# plugwatch.net
KiCad netlist of a schematic drawn in EAGLE
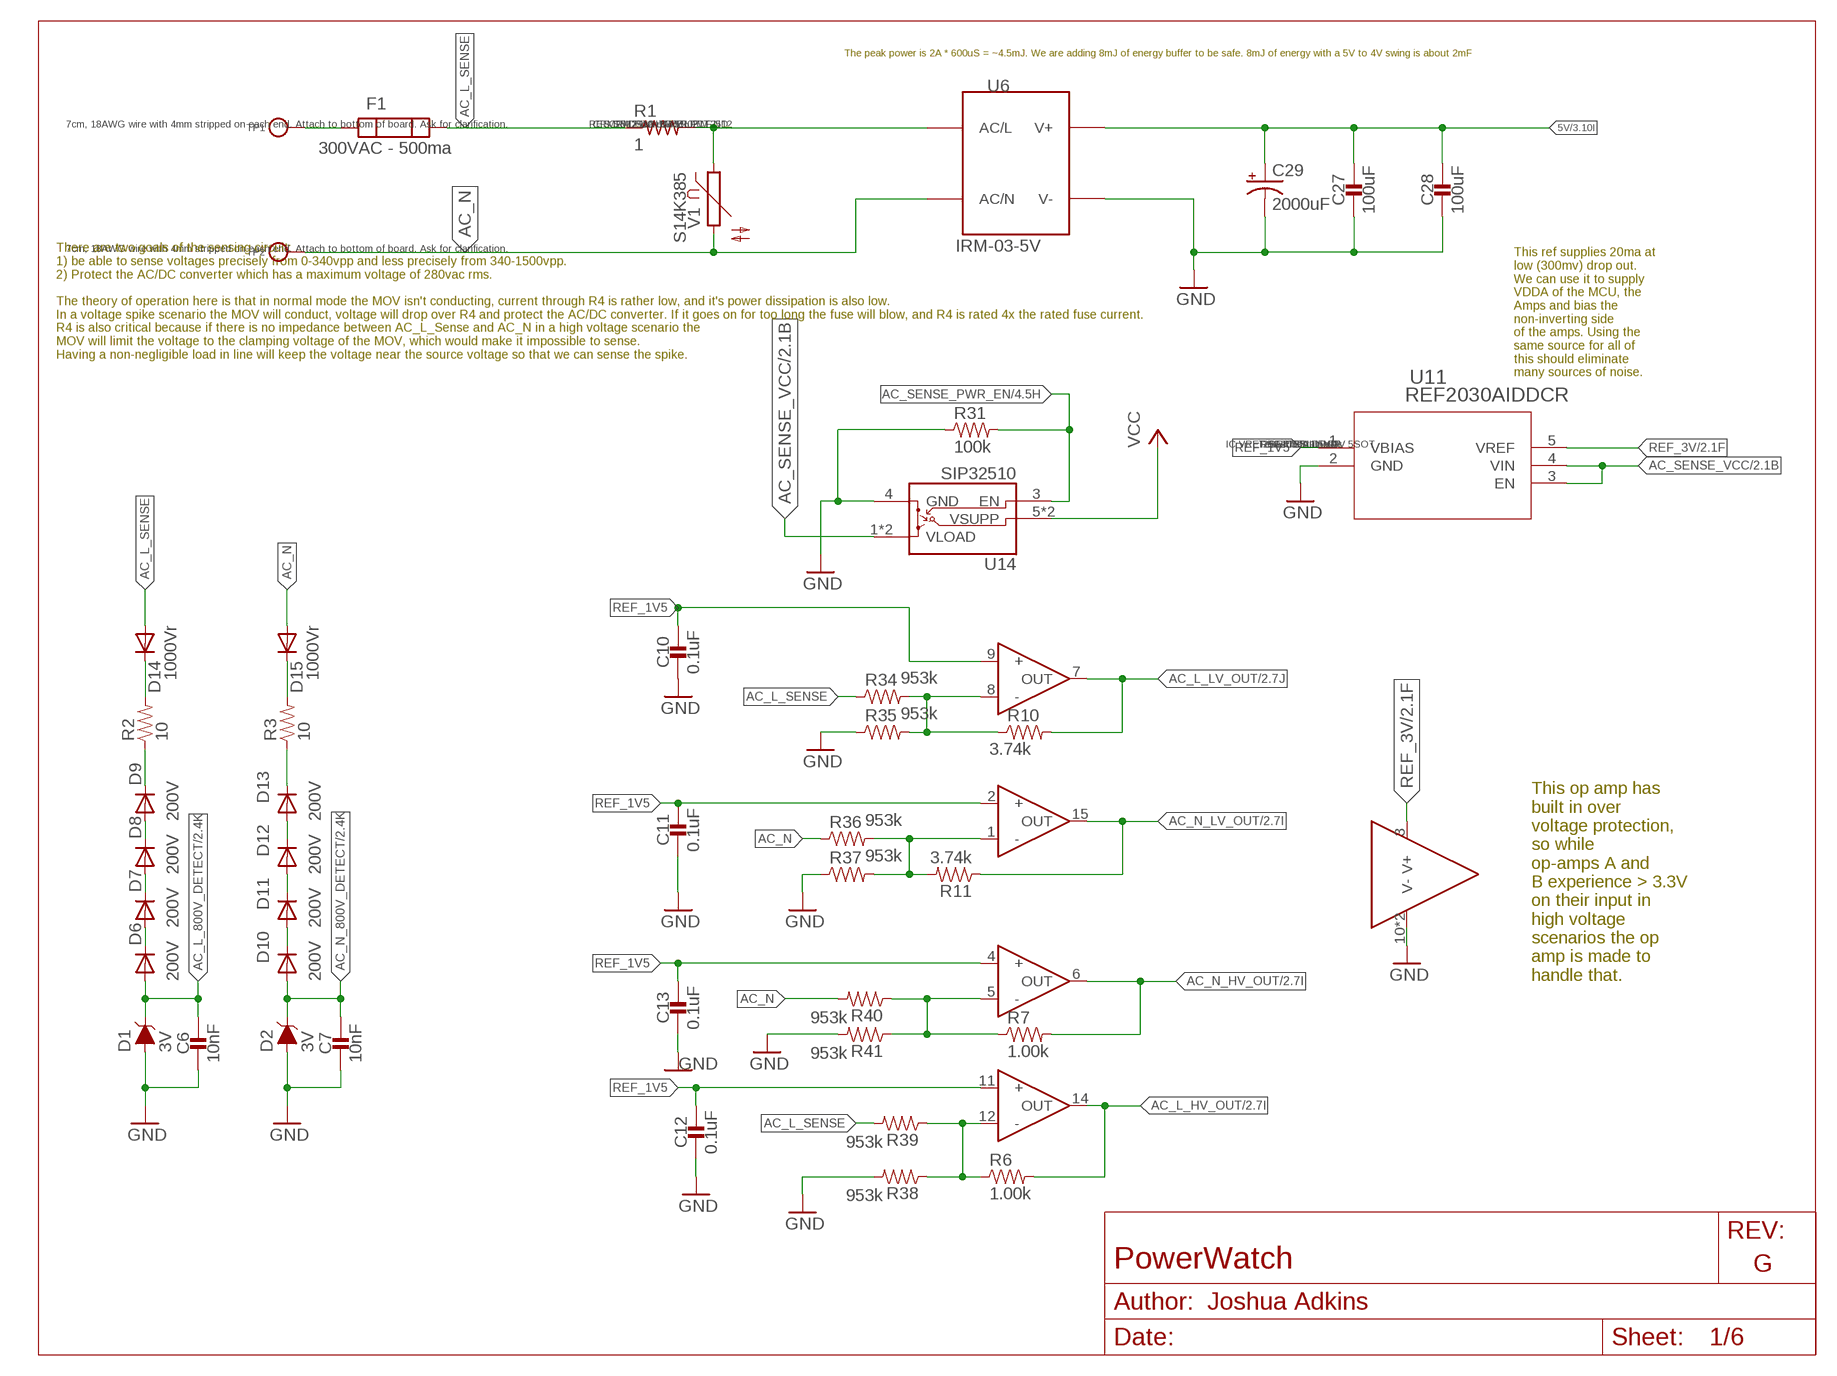
[diagram p0: schematic, sheet 1]
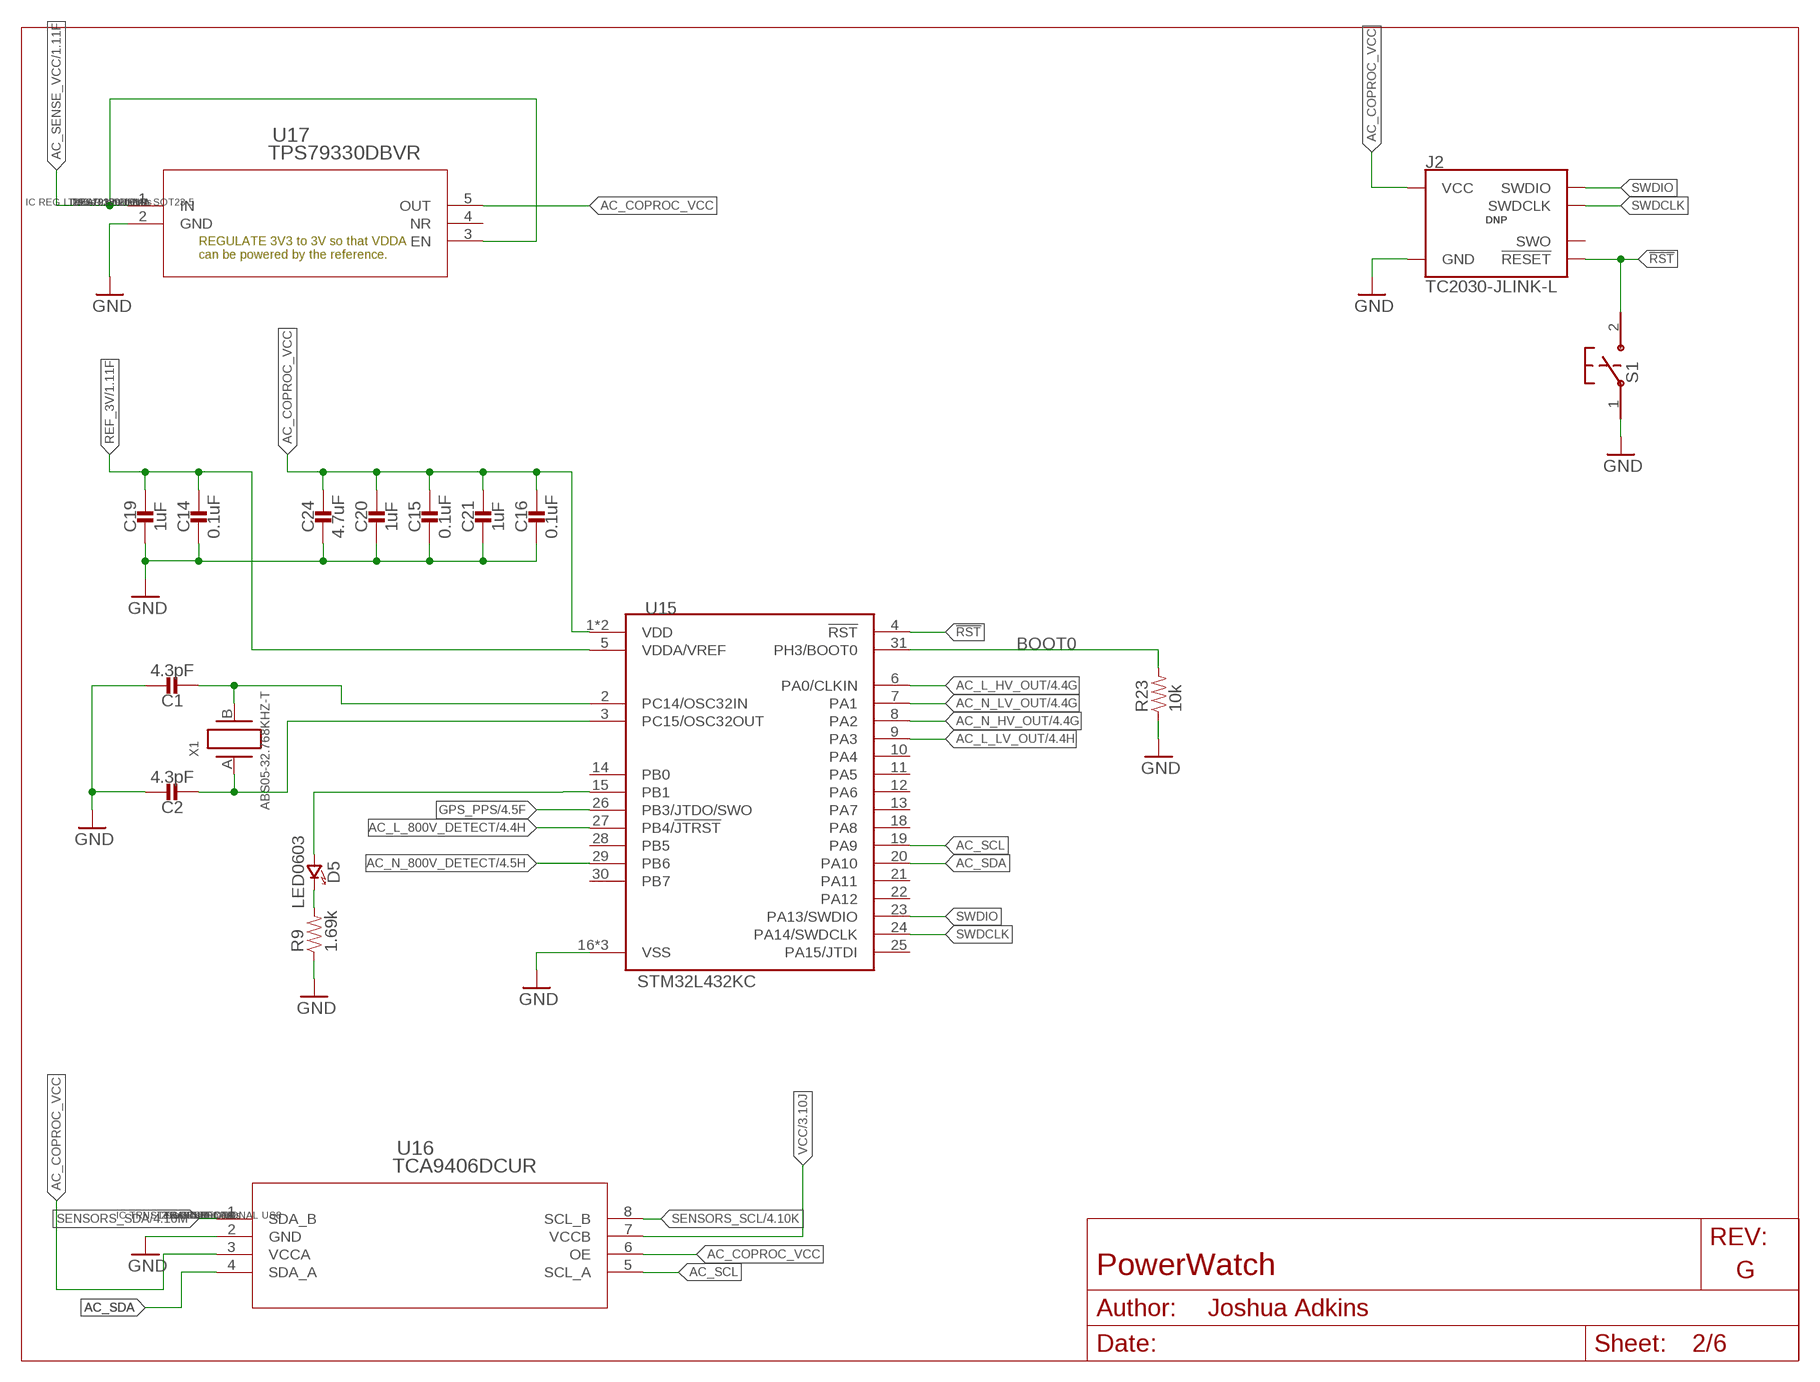
[diagram p1: schematic, sheet 2]
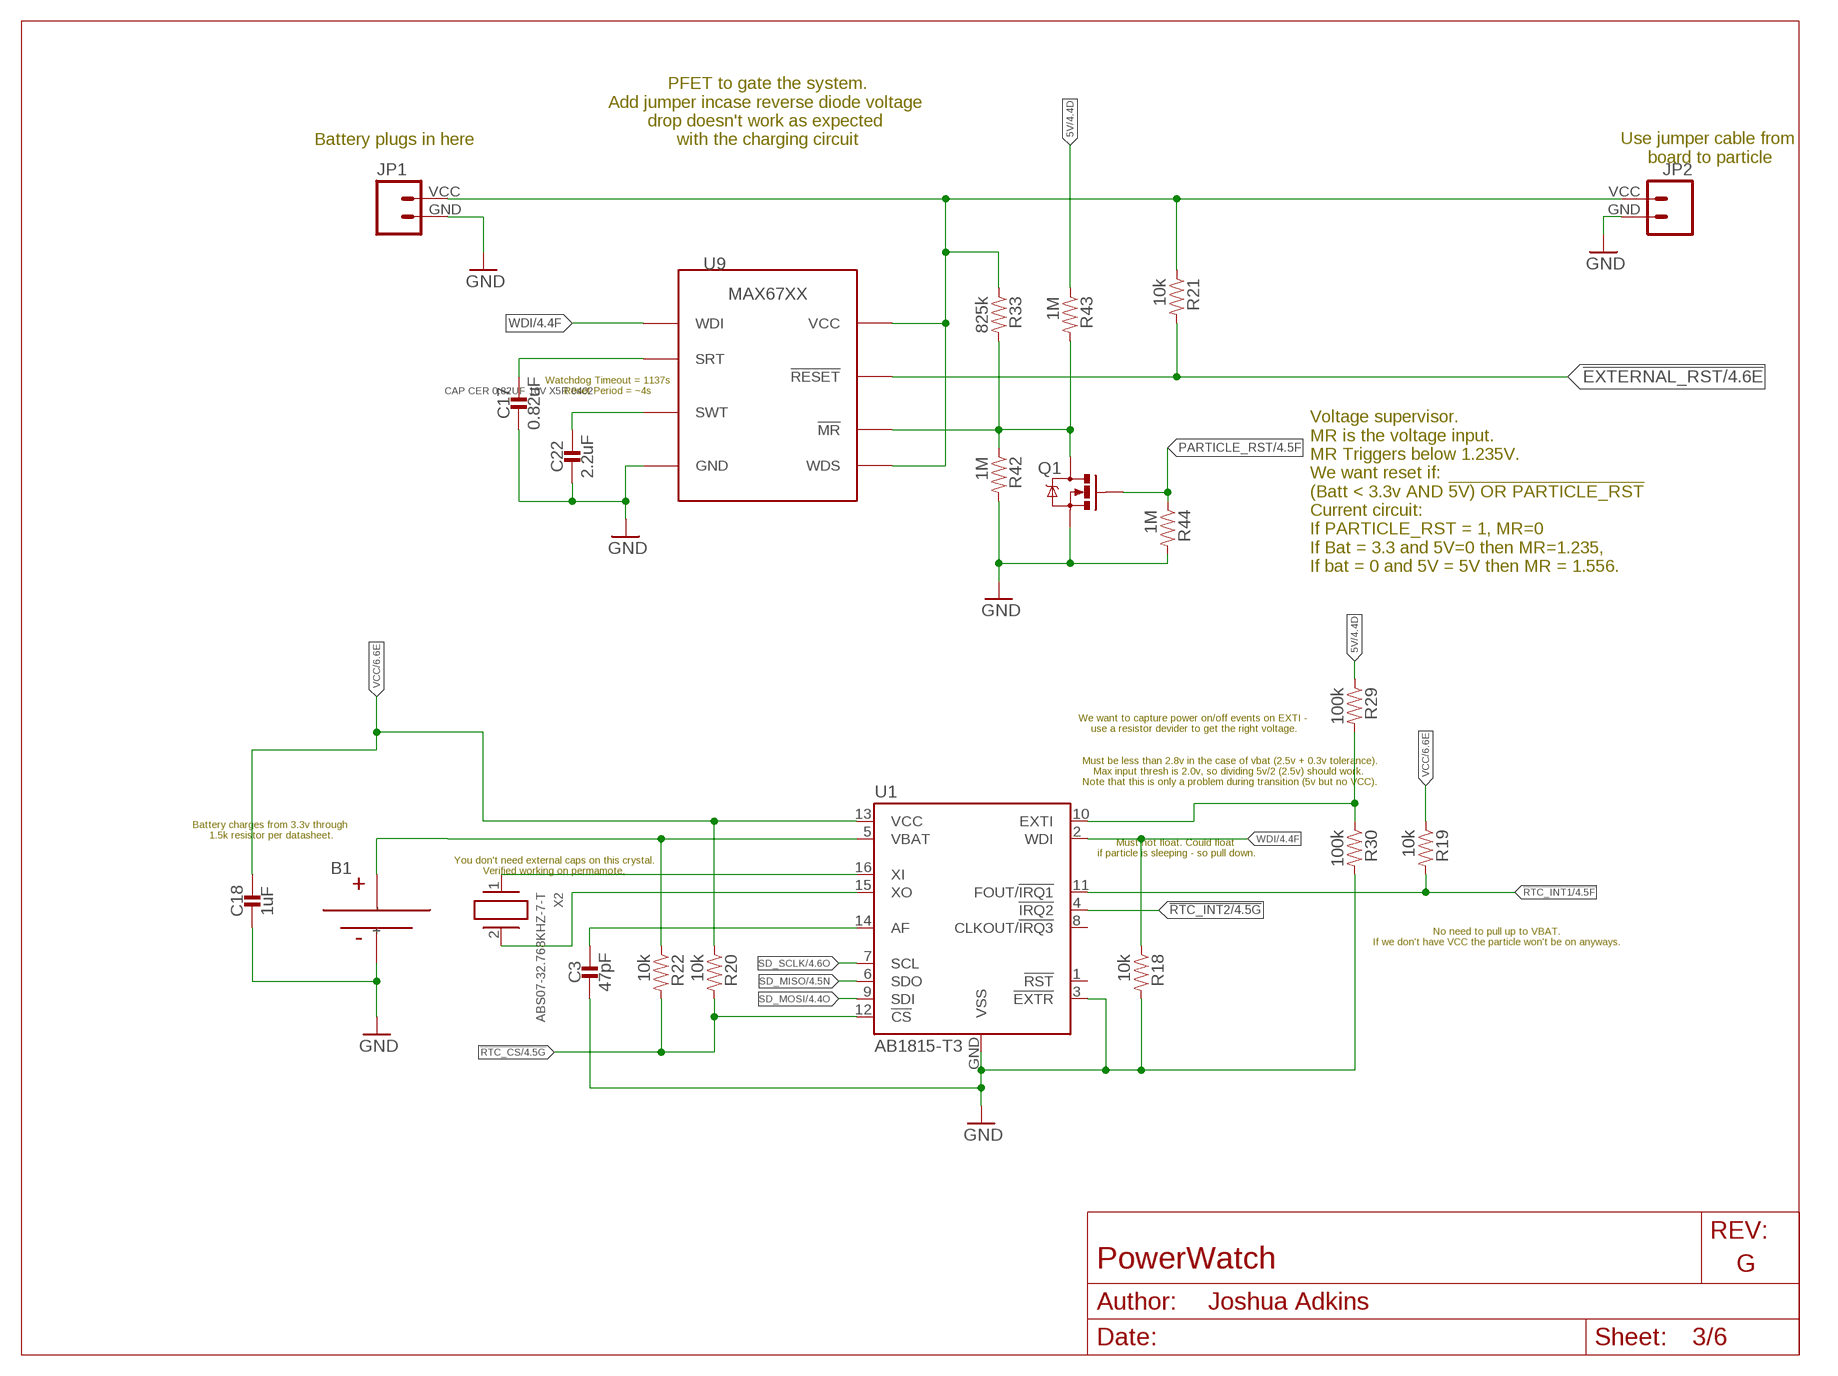
[diagram p2: schematic, sheet 3]
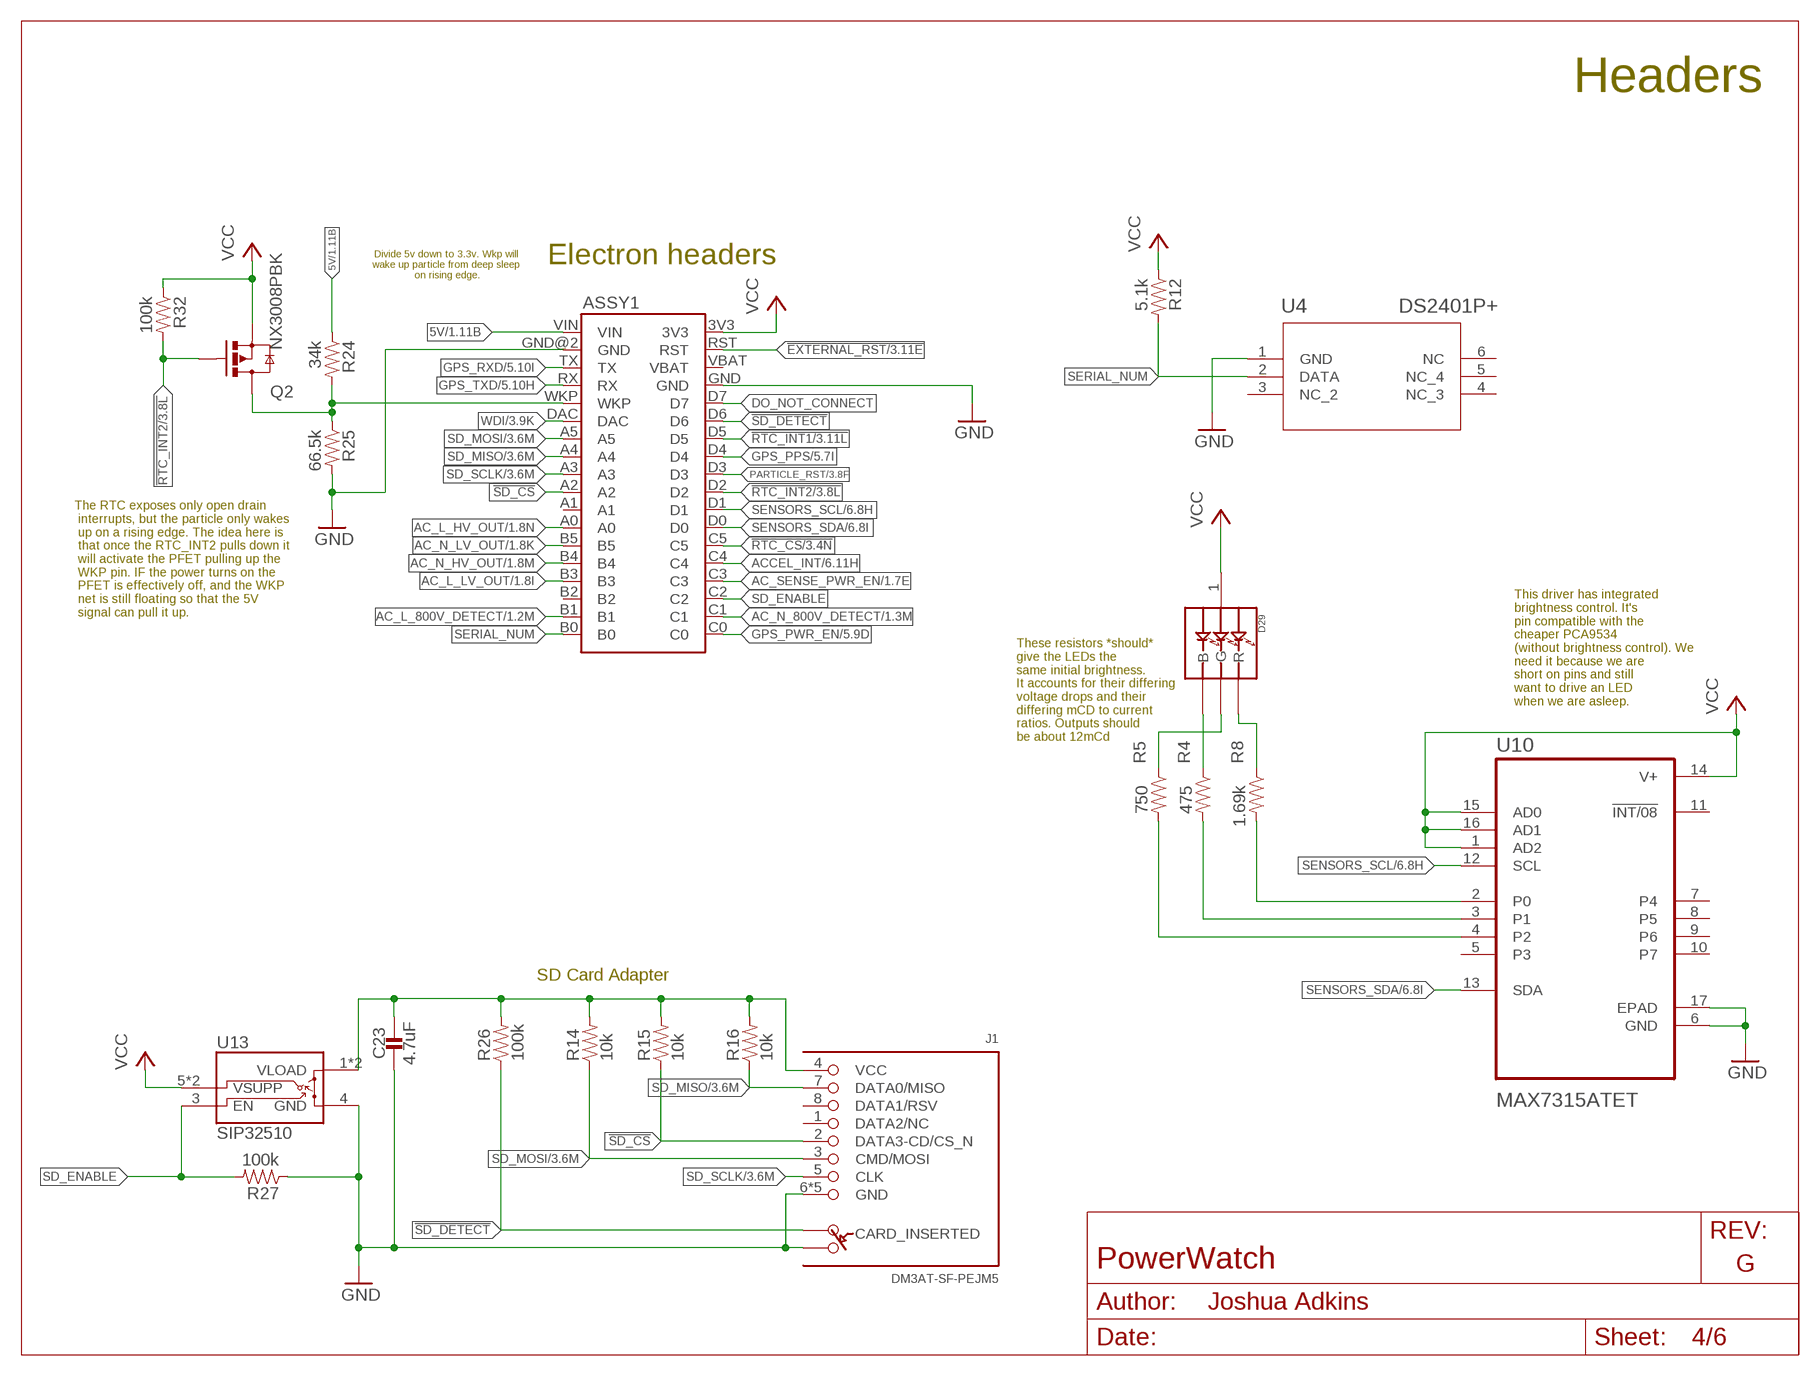
[diagram p3: schematic, sheet 4]
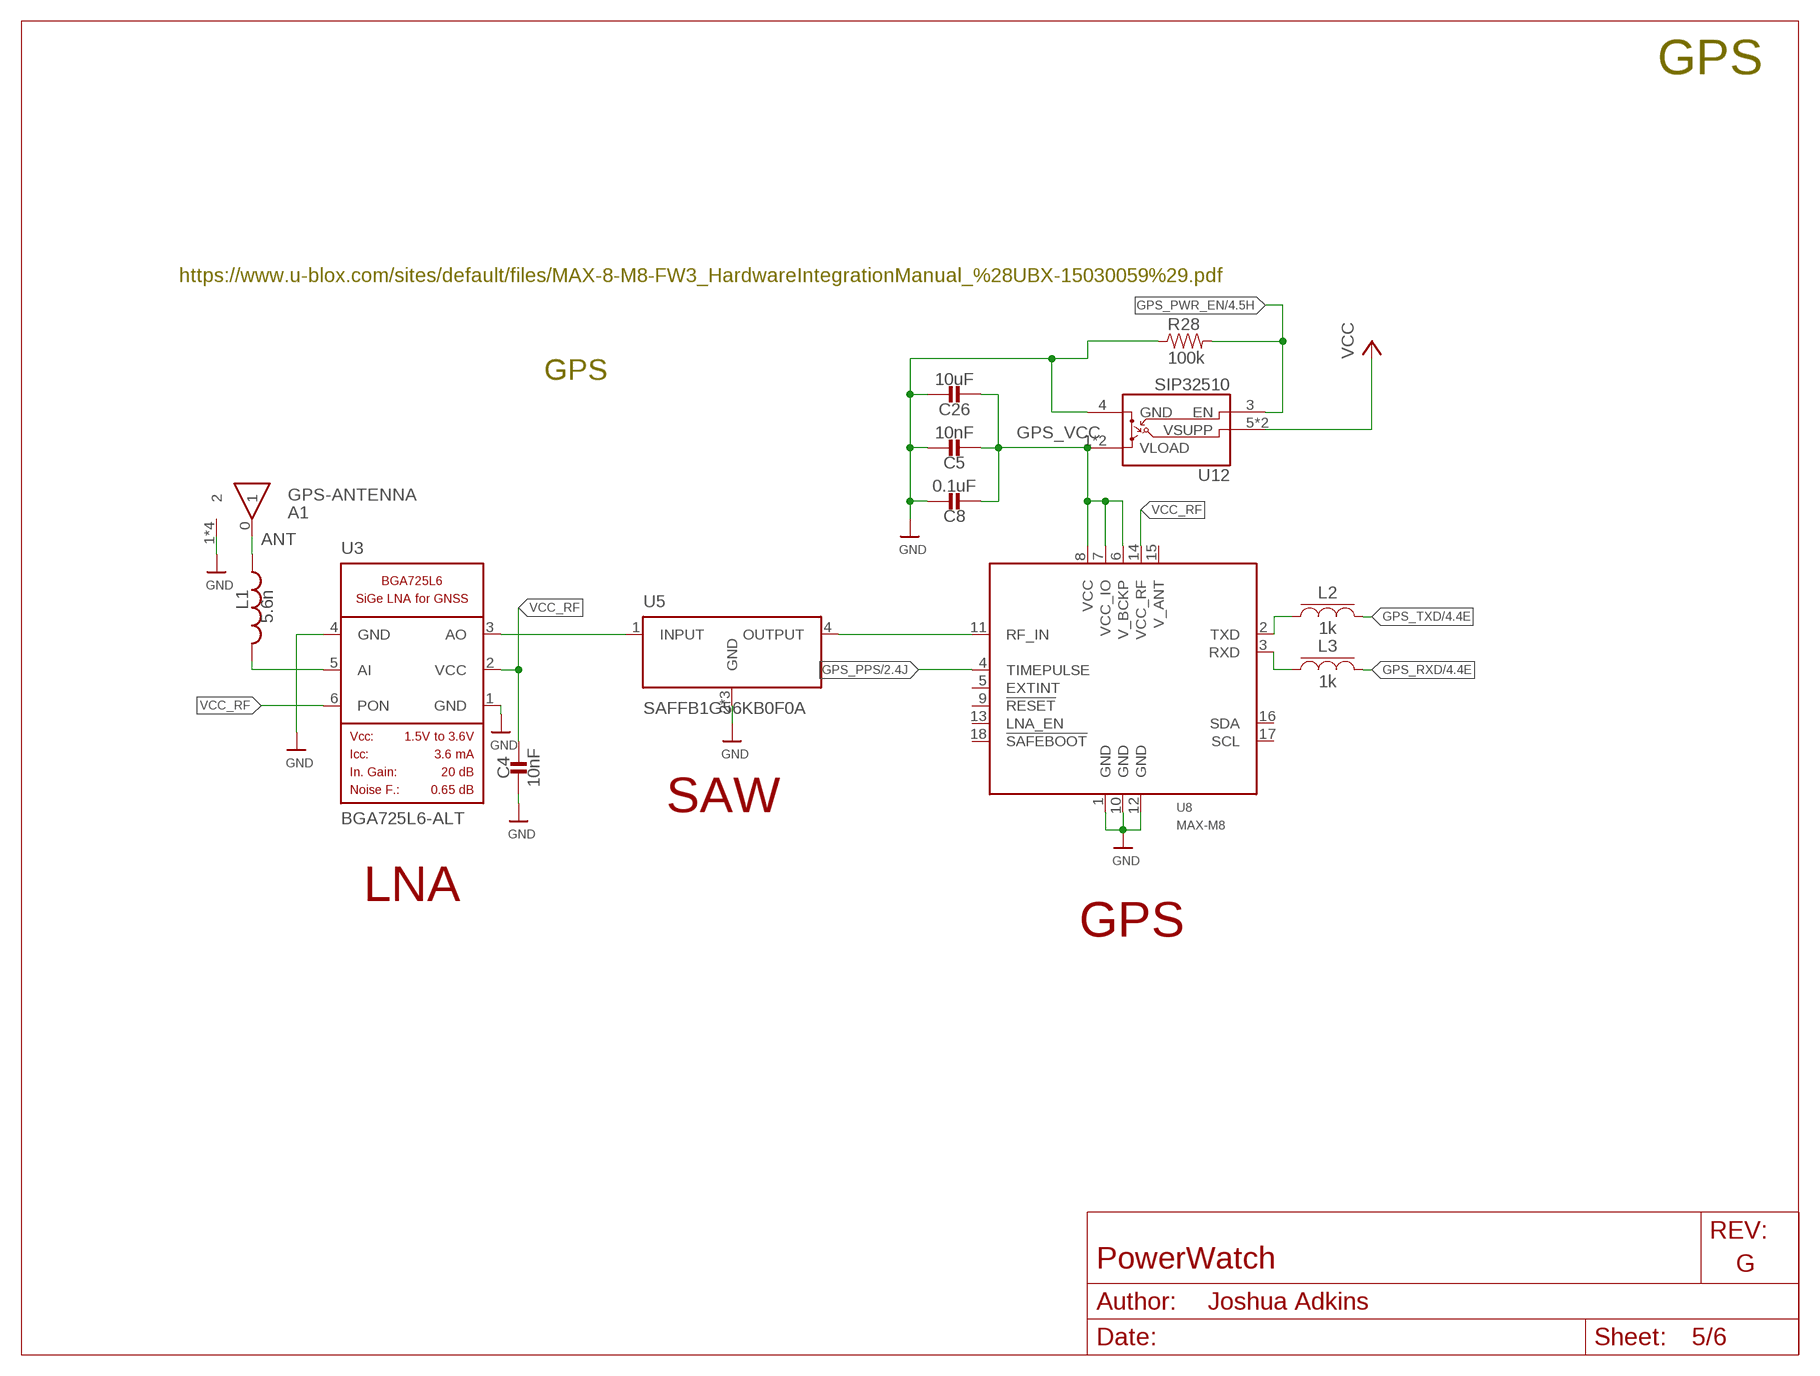
[diagram p4: schematic, sheet 5]
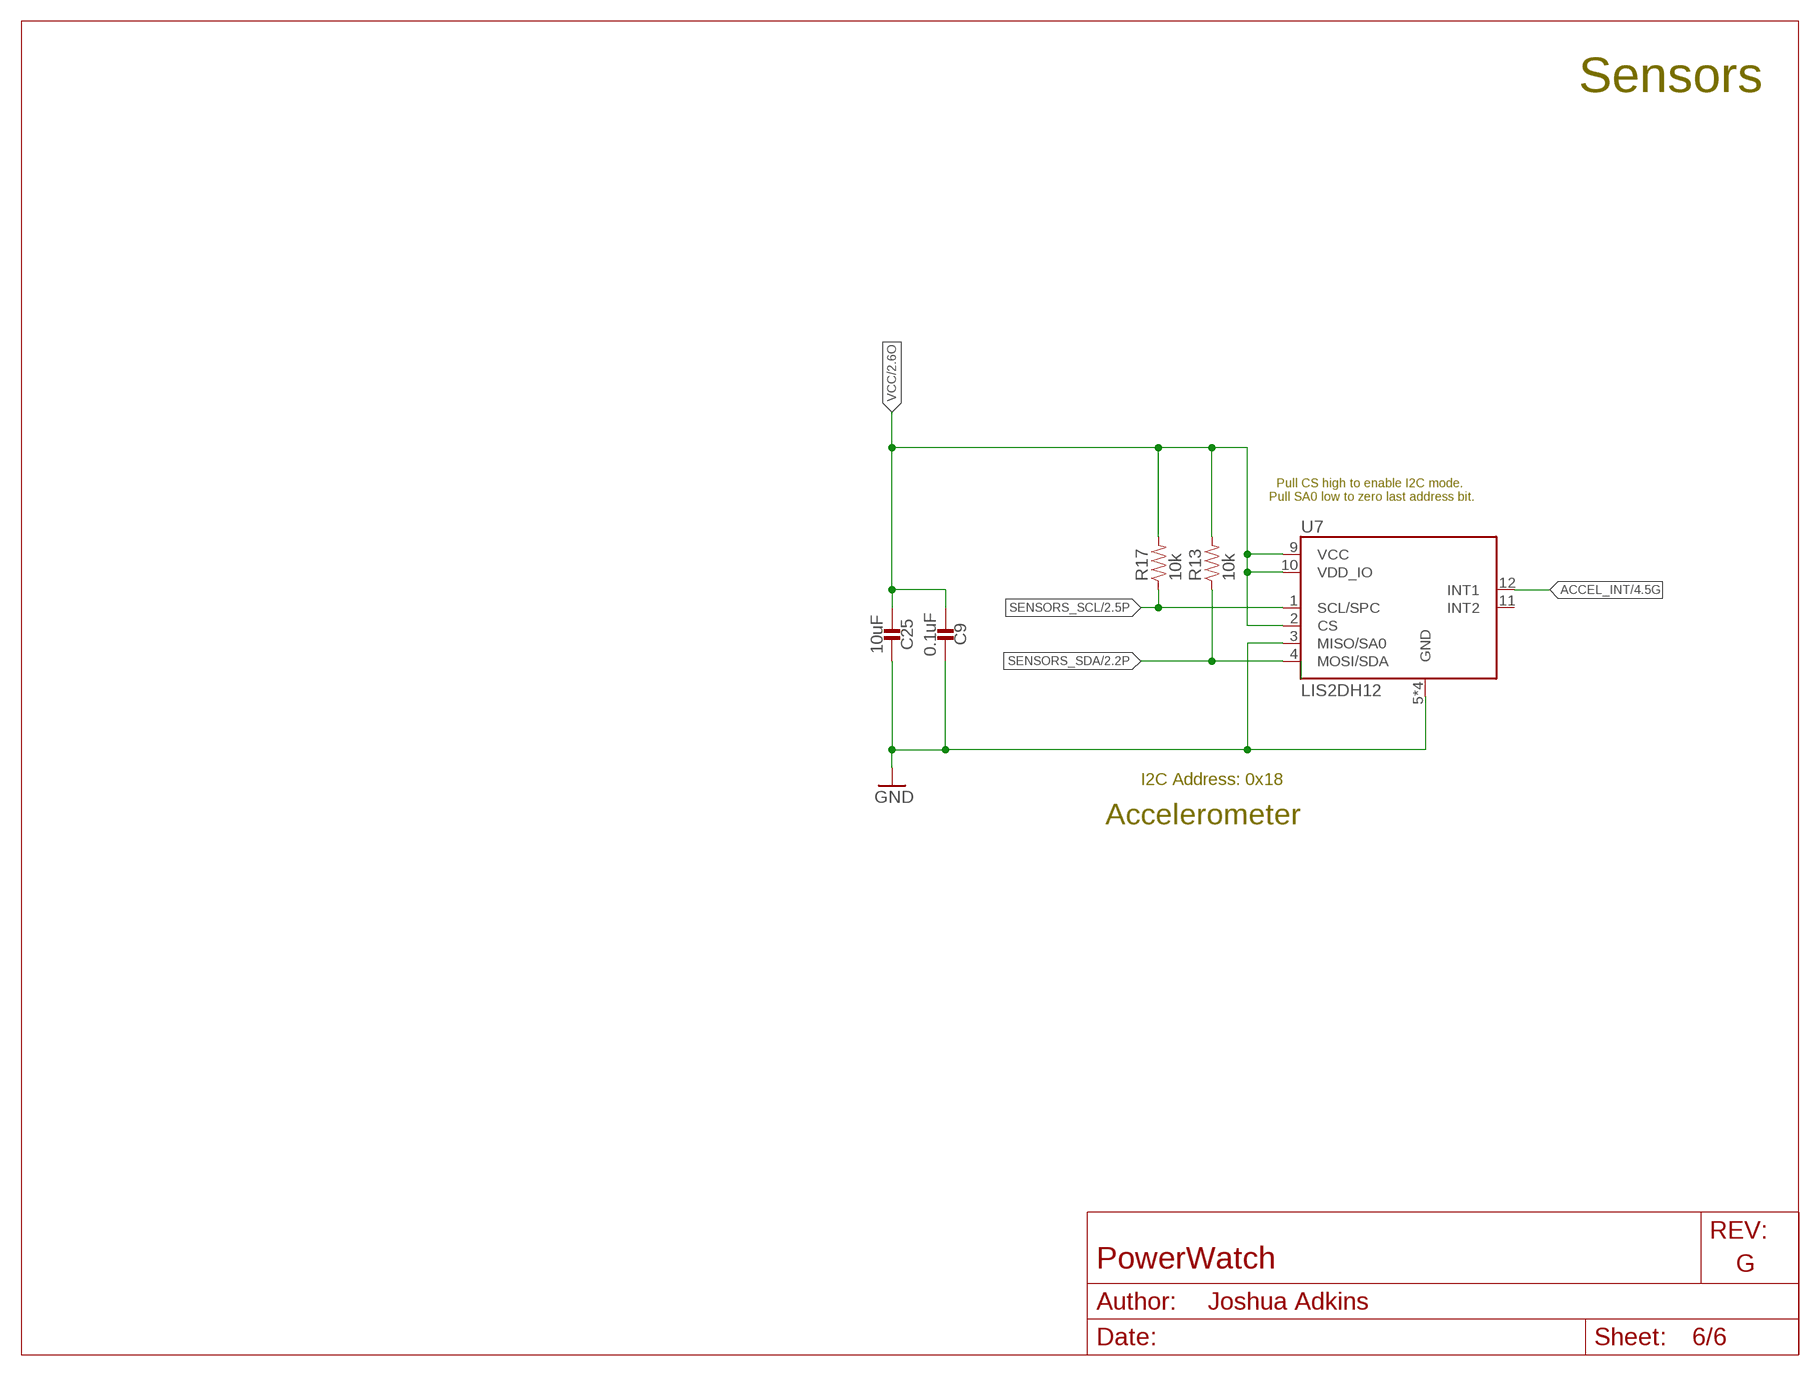
[diagram p5: schematic, sheet 6]

(export (version "E")
  (design (tool "Eeschema 10.0.6"))
  (components
    (comp (ref "A1")
      (value "GPS-ANTENNA")
      (footprint "eagle-import:ANT1818B00BT1516S")
      (description "PATCH ANT GPS/GLO CP SMD")
      (fields (field (name "MANUFACTURER") "Yageo") (field (name "MPN") "ANT1818B00BT1516S"))
      (libsource (lib "eagle-import") (part "GPS-ANTENNA"))
    )
    (comp (ref "C4")
      (value "10nF")
      (footprint "eagle-import:0402_CAP")
      (description "CAP CER 10000PF 16V X7R 0402")
      (fields
        (field (name "MANUFACTURER") "Murata Electronics North America")
        (field (name "MPN") "GRM155R71C103KA01D")
      )
      (libsource (lib "eagle-import") (part "CAPACITOR0402_CAP"))
    )
    (comp (ref "C5")
      (value "10nF")
      (footprint "eagle-import:0402_CAP")
      (description "CAP CER 10000PF 16V X7R 0402")
      (fields
        (field (name "MANUFACTURER") "Murata Electronics North America")
        (field (name "MPN") "GRM155R71C103KA01D")
      )
      (libsource (lib "eagle-import") (part "CAPACITOR0402_CAP"))
    )
    (comp (ref "C8")
      (value "0.1uF")
      (footprint "eagle-import:0402_CAP")
      (description "CAP CER 0.1UF 10V X5R 0402")
      (fields (field (name "MANUFACTURER") "Yageo") (field (name "MPN") "CC0402KRX5R6BB104"))
      (libsource (lib "eagle-import") (part "CAPACITOR0402_CAP"))
    )
    (comp (ref "C26")
      (value "10uF")
      (footprint "eagle-import:0402_CAP")
      (description "CAP CER 10UF 6.3V X5R 0402")
      (fields
        (field (name "MANUFACTURER") "Murata Electronics North America")
        (field (name "MPN") "GRJ155R60J106ME11D")
      )
      (libsource (lib "eagle-import") (part "CAPACITOR0402_CAP"))
    )
    (comp (ref "L1")
      (value "5.6n")
      (footprint "eagle-import:0402_CAP")
      (description "FIXED IND 5.6NH 1.77A 40 MOHM")
      (fields (field (name "MANUFACTURER") "Murata") (field (name "MPN") "LQW15AN5N6B80D"))
      (libsource (lib "eagle-import") (part "INDUCTOR0402"))
    )
    (comp (ref "L2")
      (value "1k")
      (footprint "eagle-import:0402_CAP")
      (description "FERRITE BEAD 1 KOHM 0402 1LN")
      (fields (field (name "MANUFACTURER") "Murata") (field (name "MPN") "BLM15HD102SN1D"))
      (libsource (lib "eagle-import") (part "FERRITE_BEAD0402"))
    )
    (comp (ref "L3")
      (value "1k")
      (footprint "eagle-import:0402_CAP")
      (description "FERRITE BEAD 1 KOHM 0402 1LN")
      (fields (field (name "MANUFACTURER") "Murata") (field (name "MPN") "BLM15HD102SN1D"))
      (libsource (lib "eagle-import") (part "FERRITE_BEAD0402"))
    )
    (comp (ref "R28")
      (value "100k")
      (footprint "eagle-import:0402_RES")
      (description "RES SMD 100K OHM 1% 1/16W 0402")
      (fields (field (name "MANUFACTURER") "Yageo") (field (name "MPN") "RC0402FR-07100KL"))
      (libsource (lib "eagle-import") (part "RESISTOR0402_RES"))
    )
    (comp (ref "U3")
      (value "BGA725L6-ALT")
      (footprint "eagle-import:LNA-TSLP-6-2-ALT")
      (description "IC AMP MMIC RF LNA 20DB TSLP-6")
      (fields (field (name "MANUFACTURER") "Infineon") (field (name "MPN") "BGA725L6E6327FTSA1"))
      (libsource (lib "eagle-import") (part "BGA725L6-ALT"))
    )
    (comp (ref "U5")
      (value "SAFFB1G56KB0F0A")
      (footprint "eagle-import:QCS5I")
      (description "FILTER SAW 1.575GHZ 5SMD")
      (fields (field (name "MANUFACTURER") "Taiyo Yuden") (field (name "MPN") "F6QA1G575H2JF-J"))
      (libsource (lib "eagle-import") (part "FILTERS"))
    )
    (comp (ref "U8")
      (value "MAX-M8")
      (footprint "eagle-import:MAX-M8")
      (description "IC RECEIVER GPS/GNSS 18LCC")
      (fields (field (name "MANUFACTURER") "u-blox") (field (name "MPN") "MAX-M8Q-0"))
      (libsource (lib "eagle-import") (part "MAX-M8"))
    )
    (comp (ref "U12")
      (value "SIP32510")
      (footprint "eagle-import:TSOT23-6")
      (fields (field (name "MANUFACTURER") "Vishay") (field (name "MPN") "SIP32510DT-T1-GE3"))
      (libsource (lib "eagle-import") (part "SIP32510"))
    )
    (comp (ref "ASSY1")
      (value "ELECTRON")
      (footprint "eagle-import:ELECTRON_SINGLE-ROW")
      (description "18 Position header")
      (fields (field (name "MANUFACTURER") "Sullins") (field (name "MPN") "PPPC181LFBN-RC"))
      (libsource (lib "eagle-import") (part "ELECTRON"))
    )
    (comp (ref "C23")
      (value "4.7uF")
      (footprint "eagle-import:0402_CAP")
      (description "CAP CER 4.7UF 6.3V X5R 0402")
      (fields (field (name "MANUFACTURER") "TDK Corporation ") (field (name "MPN") "C1005X5R0J475K050BC "))
      (libsource (lib "eagle-import") (part "CAPACITOR0402_CAP"))
    )
    (comp (ref "D29")
      (value "SML-LX0404SIUPGUSB")
      (footprint "eagle-import:1MM_SQ_4PAD")
      (fields (field (name "MANUFACTURER") "Lumex Opto"))
      (libsource (lib "eagle-import") (part "SML-LX0404SIUPGUSB"))
    )
    (comp (ref "J1")
      (value "DM3AT-SF-PEJM5")
      (footprint "eagle-import:DM3AT-SF-PEJM5")
      (fields (field (name "MANUFACTURER") "Hirose Electric Co Ltd"))
      (libsource (lib "eagle-import") (part "DM3AT-SF-PEJM5"))
    )
    (comp (ref "Q2")
      (value "NX3008PBK")
      (footprint "eagle-import:SOT23-3")
      (fields (field (name "MANUFACTURER") "Nexperia") (field (name "MPN") "NX3008PBK,215"))
      (libsource (lib "eagle-import") (part "NX3008PBK"))
    )
    (comp (ref "R4")
      (value "475")
      (footprint "eagle-import:0402_RES")
      (description "RES 475 OHM 1% 1/16W 0402")
      (fields (field (name "MANUFACTURER") "Stackpole Electronics Inc") (field (name "MPN") "RMCF0402FT475R"))
      (libsource (lib "eagle-import") (part "RESISTOR0402_RES"))
    )
    (comp (ref "R5")
      (value "750")
      (footprint "eagle-import:0402_RES")
      (description "RES SMD 750 OHM 1% 1/10W 0402")
      (fields
        (field (name "MANUFACTURER") "Panasonic Electronic Components")
        (field (name "MPN") "ERJ-2RKF7500X")
      )
      (libsource (lib "eagle-import") (part "RESISTOR0402_RES"))
    )
    (comp (ref "R8")
      (value "1.69k")
      (footprint "eagle-import:0402_RES")
      (description "RES SMD 1.69K OHM 1% 1/16W 0402")
      (fields (field (name "MANUFACTURER") "Yageo") (field (name "MPN") "RC0402FR-071K69L"))
      (libsource (lib "eagle-import") (part "RESISTOR0402_RES"))
    )
    (comp (ref "R12")
      (value "5.1k")
      (footprint "eagle-import:0402_RES")
      (description "RES SMD 5.1K OHM 1% 1/10W 0402")
      (fields
        (field (name "MANUFACTURER") "Panasonic Electronic Components")
        (field (name "MPN") "ERJ-2RKF5101X")
      )
      (libsource (lib "eagle-import") (part "RESISTOR0402_RES"))
    )
    (comp (ref "R14")
      (value "10k")
      (footprint "eagle-import:0402_RES")
      (description "RES SMD 10K OHM 1% 1/16W 0402")
      (fields
        (field (name "MANUFACTURER") "Stackpole Electronics Inc. ")
        (field (name "MPN") "RMCF0402FT10K0 ")
      )
      (libsource (lib "eagle-import") (part "RESISTOR0402_RES"))
    )
    (comp (ref "R15")
      (value "10k")
      (footprint "eagle-import:0402_RES")
      (description "RES SMD 10K OHM 1% 1/16W 0402")
      (fields
        (field (name "MANUFACTURER") "Stackpole Electronics Inc. ")
        (field (name "MPN") "RMCF0402FT10K0 ")
      )
      (libsource (lib "eagle-import") (part "RESISTOR0402_RES"))
    )
    (comp (ref "R16")
      (value "10k")
      (footprint "eagle-import:0402_RES")
      (description "RES SMD 10K OHM 1% 1/16W 0402")
      (fields
        (field (name "MANUFACTURER") "Stackpole Electronics Inc. ")
        (field (name "MPN") "RMCF0402FT10K0 ")
      )
      (libsource (lib "eagle-import") (part "RESISTOR0402_RES"))
    )
    (comp (ref "R24")
      (value "34k")
      (footprint "eagle-import:0402_RES")
      (description "RES SMD 34K OHM 1% 1/10W 0402")
      (fields
        (field (name "MANUFACTURER") "Panasonic Electronic Components")
        (field (name "MPN") "ERJ-2RKF3402X")
      )
      (libsource (lib "eagle-import") (part "RESISTOR0402_RES"))
    )
    (comp (ref "R25")
      (value "66.5k")
      (footprint "eagle-import:0402_RES")
      (description "RES SMD 66.5K OHM 1% 1/16W 0402")
      (fields (field (name "MANUFACTURER") "Yageo") (field (name "MPN") "RC0402FR-0766K5L"))
      (libsource (lib "eagle-import") (part "RESISTOR0402_RES"))
    )
    (comp (ref "R26")
      (value "100k")
      (footprint "eagle-import:0402_RES")
      (description "RES SMD 100K OHM 1% 1/16W 0402")
      (fields (field (name "MANUFACTURER") "Yageo") (field (name "MPN") "RC0402FR-07100KL"))
      (libsource (lib "eagle-import") (part "RESISTOR0402_RES"))
    )
    (comp (ref "R27")
      (value "100k")
      (footprint "eagle-import:0402_RES")
      (description "RES SMD 100K OHM 1% 1/16W 0402")
      (fields (field (name "MANUFACTURER") "Yageo") (field (name "MPN") "RC0402FR-07100KL"))
      (libsource (lib "eagle-import") (part "RESISTOR0402_RES"))
    )
    (comp (ref "R32")
      (value "100k")
      (footprint "eagle-import:0402_RES")
      (description "RES SMD 100K OHM 1% 1/16W 0402")
      (fields (field (name "MANUFACTURER") "Yageo") (field (name "MPN") "RC0402FR-07100KL"))
      (libsource (lib "eagle-import") (part "RESISTOR0402_RES"))
    )
    (comp (ref "U4")
      (value "DS2401P+")
      (footprint "eagle-import:21-0382")
      (fields (field (name "MANUFACTURER") "Maxim Integrated") (field (name "SPICEPREFIX") "X"))
      (libsource (lib "eagle-import") (part "DS2401P+"))
    )
    (comp (ref "U10")
      (value "MAX7315ATET")
      (footprint "eagle-import:QFN50P300X300X80-17N")
      (description "IC I/O EXPANDER I2C 8B 16TQFN")
      (fields
        (field (name "DIGI-KEY_PART_NUMBER") "MAX7315ATE+-ND")
        (field (name "MF") "Maxim Integrated")
        (field (name "MP") "MAX7315ATE+")
        (field (name "DIGIKEY") "MAX7315ATE+-ND")
        (field (name "MANUFACTURER") "Maxim Integrated")
        (field (name "MPN") "MAX7315ATE+")
      )
      (libsource (lib "eagle-import") (part "MAX7315ATET"))
    )
    (comp (ref "U13")
      (value "SIP32510")
      (footprint "eagle-import:TSOT23-6")
      (fields (field (name "MANUFACTURER") "Vishay") (field (name "MPN") "SIP32510DT-T1-GE3"))
      (libsource (lib "eagle-import") (part "SIP32510"))
    )
    (comp (ref "C1")
      (value "4.3pF")
      (footprint "eagle-import:0402_CAP")
      (description "CAP CER 4.3PF 50V C0G/NP0 0402")
      (fields
        (field (name "MANUFACTURER") "Murata Electronics North America")
        (field (name "MPN") "GJM1555C1H4R3CB01D")
      )
      (libsource (lib "eagle-import") (part "CAPACITOR0402_CAP"))
    )
    (comp (ref "C2")
      (value "4.3pF")
      (footprint "eagle-import:0402_CAP")
      (description "CAP CER 4.3PF 50V C0G/NP0 0402")
      (fields
        (field (name "MANUFACTURER") "Murata Electronics North America")
        (field (name "MPN") "GJM1555C1H4R3CB01D")
      )
      (libsource (lib "eagle-import") (part "CAPACITOR0402_CAP"))
    )
    (comp (ref "C14")
      (value "0.1uF")
      (footprint "eagle-import:0402_CAP")
      (description "CAP CER 0.1UF 10V X5R 0402")
      (fields (field (name "MANUFACTURER") "Yageo") (field (name "MPN") "CC0402KRX5R6BB104"))
      (libsource (lib "eagle-import") (part "CAPACITOR0402_CAP"))
    )
    (comp (ref "C15")
      (value "0.1uF")
      (footprint "eagle-import:0402_CAP")
      (description "CAP CER 0.1UF 10V X5R 0402")
      (fields (field (name "MANUFACTURER") "Yageo") (field (name "MPN") "CC0402KRX5R6BB104"))
      (libsource (lib "eagle-import") (part "CAPACITOR0402_CAP"))
    )
    (comp (ref "C16")
      (value "0.1uF")
      (footprint "eagle-import:0402_CAP")
      (description "CAP CER 0.1UF 10V X5R 0402")
      (fields (field (name "MANUFACTURER") "Yageo") (field (name "MPN") "CC0402KRX5R6BB104"))
      (libsource (lib "eagle-import") (part "CAPACITOR0402_CAP"))
    )
    (comp (ref "C19")
      (value "1uF")
      (footprint "eagle-import:0402_CAP")
      (description "CAP CER 1UF 10V X7S 0402")
      (fields
        (field (name "MANUFACTURER") "Murata Electronics North America")
        (field (name "MPN") "GCM155C71A105KE38D")
      )
      (libsource (lib "eagle-import") (part "CAPACITOR0402_CAP"))
    )
    (comp (ref "C20")
      (value "1uF")
      (footprint "eagle-import:0402_CAP")
      (description "CAP CER 1UF 10V X7S 0402")
      (fields
        (field (name "MANUFACTURER") "Murata Electronics North America")
        (field (name "MPN") "GCM155C71A105KE38D")
      )
      (libsource (lib "eagle-import") (part "CAPACITOR0402_CAP"))
    )
    (comp (ref "C21")
      (value "1uF")
      (footprint "eagle-import:0402_CAP")
      (description "CAP CER 1UF 10V X7S 0402")
      (fields
        (field (name "MANUFACTURER") "Murata Electronics North America")
        (field (name "MPN") "GCM155C71A105KE38D")
      )
      (libsource (lib "eagle-import") (part "CAPACITOR0402_CAP"))
    )
    (comp (ref "C24")
      (value "4.7uF")
      (footprint "eagle-import:0402_CAP")
      (description "CAP CER 4.7UF 6.3V X5R 0402")
      (fields (field (name "MANUFACTURER") "TDK Corporation ") (field (name "MPN") "C1005X5R0J475K050BC "))
      (libsource (lib "eagle-import") (part "CAPACITOR0402_CAP"))
    )
    (comp (ref "D5")
      (value "LED0603")
      (footprint "eagle-import:LED-0603")
      (description "LED RED DIFFUSED 1608 SMD")
      (fields
        (field (name "DIGIKEY") "SML-D12U1WT86CT-ND")
        (field (name "MANUFACTURER") "Rohm Semiconductor")
        (field (name "MPN") "SML-D12U1WT86")
      )
      (libsource (lib "eagle-import") (part "LED0603"))
    )
    (comp (ref "J2")
      (value "TC2030-JLINK-L")
      (footprint "eagle-import:TC2030-IDC")
      (fields (field (name "DIGIKEY") "DNP") (field (name "MANUFACTURER") "DNP") (field (name "MPN") "DNP"))
      (libsource (lib "eagle-import") (part "TC2030-JLINK-L"))
    )
    (comp (ref "R9")
      (value "1.69k")
      (footprint "eagle-import:0402_RES")
      (description "RES SMD 1.69K OHM 1% 1/16W 0402")
      (fields (field (name "MANUFACTURER") "Yageo") (field (name "MPN") "RC0402FR-071K69L"))
      (libsource (lib "eagle-import") (part "RESISTOR0402_RES"))
    )
    (comp (ref "R23")
      (value "10k")
      (footprint "eagle-import:0402_RES")
      (description "RES SMD 10K OHM 1% 1/16W 0402")
      (fields
        (field (name "MANUFACTURER") "Stackpole Electronics Inc.  ")
        (field (name "MPN") "RMCF0402FT10K0  ")
      )
      (libsource (lib "eagle-import") (part "RESISTOR0402_RES"))
    )
    (comp (ref "S1")
      (value "B3U-1000P")
      (footprint "eagle-import:B3U-1000P")
      (fields (field (name "MANUFACTURER") "Omron"))
      (libsource (lib "eagle-import") (part "B3U-1000P"))
    )
    (comp (ref "U15")
      (value "STM32L432KC")
      (footprint "eagle-import:UQFN-32")
      (fields (field (name "MANUFACTURER") "STMicroelectronics") (field (name "MPN") "STM32L432KCU6"))
      (libsource (lib "eagle-import") (part "STM32L432KC"))
    )
    (comp (ref "U16")
      (value "TCA9406DCUR")
      (footprint "eagle-import:DCU8")
      (description "IC TRNSLTR BIDIRECTIONAL US8")
      (fields
        (field (name "DIGIKEY") "296-28109-1-ND")
        (field (name "MANUFACTURER") "Texas Instruments")
        (field (name "MPN") "TCA9406DCUR")
      )
      (libsource (lib "eagle-import") (part "TCA9406DCUR"))
    )
    (comp (ref "U17")
      (value "TPS79330DBVR")
      (footprint "eagle-import:DBV5")
      (description "IC REG LINEAR 3V 200MA SOT23-5")
      (fields
        (field (name "DIGIKEY") "296-12159-1-ND")
        (field (name "MANUFACTURER") "Texas Instruments")
        (field (name "MPN") "TPS79330DBVR")
      )
      (libsource (lib "eagle-import") (part "TPS79330DBVR"))
    )
    (comp (ref "X1")
      (value "ABS05-32.768KHZ-T")
      (footprint "eagle-import:ABS05")
      (fields (field (name "MANUFACTURER") "Abracon"))
      (libsource (lib "eagle-import") (part "ABS05-32.768KHZ-T"))
    )
    (comp (ref "C6")
      (value "10nF")
      (footprint "eagle-import:0402_CAP")
      (description "CAP CER 10000PF 16V X7R 0402")
      (fields
        (field (name "MANUFACTURER") "Murata Electronics North America")
        (field (name "MPN") "GRM155R71C103KA01D")
      )
      (libsource (lib "eagle-import") (part "CAPACITOR0402_CAP"))
    )
    (comp (ref "C7")
      (value "10nF")
      (footprint "eagle-import:0402_CAP")
      (description "CAP CER 10000PF 16V X7R 0402")
      (fields
        (field (name "MANUFACTURER") "Murata Electronics North America")
        (field (name "MPN") "GRM155R71C103KA01D")
      )
      (libsource (lib "eagle-import") (part "CAPACITOR0402_CAP"))
    )
    (comp (ref "C10")
      (value "0.1uF")
      (footprint "eagle-import:0402_CAP")
      (description "CAP CER 0.1UF 10V X5R 0402")
      (fields (field (name "MANUFACTURER") "Yageo") (field (name "MPN") "CC0402KRX5R6BB104"))
      (libsource (lib "eagle-import") (part "CAPACITOR0402_CAP"))
    )
    (comp (ref "C11")
      (value "0.1uF")
      (footprint "eagle-import:0402_CAP")
      (description "CAP CER 0.1UF 10V X5R 0402")
      (fields (field (name "MANUFACTURER") "Yageo") (field (name "MPN") "CC0402KRX5R6BB104"))
      (libsource (lib "eagle-import") (part "CAPACITOR0402_CAP"))
    )
    (comp (ref "C12")
      (value "0.1uF")
      (footprint "eagle-import:0402_CAP")
      (description "CAP CER 0.1UF 10V X5R 0402")
      (fields (field (name "MANUFACTURER") "Yageo") (field (name "MPN") "CC0402KRX5R6BB104"))
      (libsource (lib "eagle-import") (part "CAPACITOR0402_CAP"))
    )
    (comp (ref "C13")
      (value "0.1uF")
      (footprint "eagle-import:0402_CAP")
      (description "CAP CER 0.1UF 10V X5R 0402")
      (fields (field (name "MANUFACTURER") "Yageo") (field (name "MPN") "CC0402KRX5R6BB104"))
      (libsource (lib "eagle-import") (part "CAPACITOR0402_CAP"))
    )
    (comp (ref "C27")
      (value "100uF")
      (footprint "eagle-import:1210_CAP")
      (description "CAP CER 100UF 6.3V X7S 1210")
      (fields
        (field (name "MANUFACTURER") "Murata Electronics North America")
        (field (name "MPN") "GRM32EC70J107ME15L")
      )
      (libsource (lib "eagle-import") (part "CAPACITOR1210_CAP"))
    )
    (comp (ref "C28")
      (value "100uF")
      (footprint "eagle-import:1210_CAP")
      (description "CAP CER 100UF 6.3V X7S 1210")
      (fields
        (field (name "MANUFACTURER") "Murata Electronics North America")
        (field (name "MPN") "GRM32EC70J107ME15L")
      )
      (libsource (lib "eagle-import") (part "CAPACITOR1210_CAP"))
    )
    (comp (ref "C29")
      (value "2000uF")
      (footprint "eagle-import:E5-13")
      (description "CAP ALUM 2000UF 20% 6.3V T/H")
      (fields
        (field (name "MANUFACTURER") "Panasonic Electronic Components")
        (field (name "MPN") "EEU-FS0J202B")
      )
      (libsource (lib "eagle-import") (part "CPOL-USE5-13"))
    )
    (comp (ref "D1")
      (value "3V")
      (footprint "eagle-import:SOD-323")
      (description "DIODE ZENER 3V 300MW SOD323")
      (fields
        (field (name "DIGIKEY") "MM3Z3V0ST1GOSCT-ND")
        (field (name "MANUFACTURER") "ON Semiconductor")
        (field (name "MPN") "MM3Z3V0ST1G")
      )
      (libsource (lib "eagle-import") (part "DIODE-ZENER-MM3Z3V3T1G"))
    )
    (comp (ref "D2")
      (value "3V")
      (footprint "eagle-import:SOD-323")
      (description "DIODE ZENER 3V 300MW SOD323")
      (fields
        (field (name "DIGIKEY") "MM3Z3V0ST1GOSCT-ND")
        (field (name "MANUFACTURER") "ON Semiconductor")
        (field (name "MPN") "MM3Z3V0ST1G")
      )
      (libsource (lib "eagle-import") (part "DIODE-ZENER-MM3Z3V3T1G"))
    )
    (comp (ref "D6")
      (value "200V")
      (footprint "eagle-import:DO214AA")
      (description "DIODE ZENER 200V 3W DO214AA")
      (fields
        (field (name "DIGIKEY") "1PGSMB5956R5GCT-ND")
        (field (name "MANUFACTURER") "Taiwan Semiconductor Corporation")
        (field (name "MPN") "1PGSMB5956 R5G")
      )
      (libsource (lib "eagle-import") (part "DIODE-DO214AA"))
    )
    (comp (ref "D7")
      (value "200V")
      (footprint "eagle-import:DO214AA")
      (description "DIODE ZENER 200V 3W DO214AA")
      (fields
        (field (name "DIGIKEY") "1PGSMB5956R5GCT-ND")
        (field (name "MANUFACTURER") "Taiwan Semiconductor Corporation")
        (field (name "MPN") "1PGSMB5956 R5G")
      )
      (libsource (lib "eagle-import") (part "DIODE-DO214AA"))
    )
    (comp (ref "D8")
      (value "200V")
      (footprint "eagle-import:DO214AA")
      (description "DIODE ZENER 200V 3W DO214AA")
      (fields
        (field (name "DIGIKEY") "1PGSMB5956R5GCT-ND")
        (field (name "MANUFACTURER") "Taiwan Semiconductor Corporation")
        (field (name "MPN") "1PGSMB5956 R5G")
      )
      (libsource (lib "eagle-import") (part "DIODE-DO214AA"))
    )
    (comp (ref "D9")
      (value "200V")
      (footprint "eagle-import:DO214AA")
      (description "DIODE ZENER 200V 3W DO214AA")
      (fields
        (field (name "DIGIKEY") "1PGSMB5956R5GCT-ND")
        (field (name "MANUFACTURER") "Taiwan Semiconductor Corporation")
        (field (name "MPN") "1PGSMB5956 R5G")
      )
      (libsource (lib "eagle-import") (part "DIODE-DO214AA"))
    )
    (comp (ref "D10")
      (value "200V")
      (footprint "eagle-import:DO214AA")
      (description "DIODE ZENER 200V 3W DO214AA")
      (fields
        (field (name "DIGIKEY") "1PGSMB5956R5GCT-ND")
        (field (name "MANUFACTURER") "Taiwan Semiconductor Corporation")
        (field (name "MPN") "1PGSMB5956 R5G")
      )
      (libsource (lib "eagle-import") (part "DIODE-DO214AA"))
    )
    (comp (ref "D11")
      (value "200V")
      (footprint "eagle-import:DO214AA")
      (description "DIODE ZENER 200V 3W DO214AA")
      (fields
        (field (name "DIGIKEY") "1PGSMB5956R5GCT-ND")
        (field (name "MANUFACTURER") "Taiwan Semiconductor Corporation")
        (field (name "MPN") "1PGSMB5956 R5G")
      )
      (libsource (lib "eagle-import") (part "DIODE-DO214AA"))
    )
    (comp (ref "D12")
      (value "200V")
      (footprint "eagle-import:DO214AA")
      (description "DIODE ZENER 200V 3W DO214AA")
      (fields
        (field (name "DIGIKEY") "1PGSMB5956R5GCT-ND")
        (field (name "MANUFACTURER") "Taiwan Semiconductor Corporation")
        (field (name "MPN") "1PGSMB5956 R5G")
      )
      (libsource (lib "eagle-import") (part "DIODE-DO214AA"))
    )
    (comp (ref "D13")
      (value "200V")
      (footprint "eagle-import:DO214AA")
      (description "DIODE ZENER 200V 3W DO214AA")
      (fields
        (field (name "DIGIKEY") "1PGSMB5956R5GCT-ND")
        (field (name "MANUFACTURER") "Taiwan Semiconductor Corporation")
        (field (name "MPN") "1PGSMB5956 R5G")
      )
      (libsource (lib "eagle-import") (part "DIODE-DO214AA"))
    )
    (comp (ref "D14")
      (value "1000Vr")
      (footprint "eagle-import:DO214AC")
      (description "DIODE GEN PURP 1KV 1A SMA")
      (fields
        (field (name "DIGIKEY") "S1M-FDICT-ND")
        (field (name "MANUFACTURER") "Diodes Incorporated")
        (field (name "MPN") "S1M-13-F")
      )
      (libsource (lib "eagle-import") (part "DIODE-DO214AC"))
    )
    (comp (ref "D15")
      (value "1000Vr")
      (footprint "eagle-import:DO214AC")
      (description "DIODE GEN PURP 1KV 1A SMA")
      (fields
        (field (name "DIGIKEY") "S1M-FDICT-ND")
        (field (name "MANUFACTURER") "Diodes Incorporated")
        (field (name "MPN") "S1M-13-F")
      )
      (libsource (lib "eagle-import") (part "DIODE-DO214AC"))
    )
    (comp (ref "F1")
      (value "300VAC - 500ma")
      (footprint "eagle-import:MIRCRO_FUSE_5MM")
      (description "FUSE BRD MNT 500MA 350VAC 100VDC")
      (fields (field (name "MANUFACTURER") "Bel Fuse Inc") (field (name "MPN") "0697H0500-01"))
      (libsource (lib "eagle-import") (part "MICRO_FUSE500MA_350VAC"))
    )
    (comp (ref "R1")
      (value "1")
      (footprint "eagle-import:R2512")
      (description "RES SMD 1 OHM 5% 2W 2512")
      (fields
        (field (name "DIGIKEY") "CRM2512-JW-1R0ELFCT-ND")
        (field (name "MANUFACTURER") "Bourns Inc.")
        (field (name "MPN") "CRM2512-JW-1R0ELF")
      )
      (libsource (lib "eagle-import") (part "R-US_R2512"))
    )
    (comp (ref "R2")
      (value "10")
      (footprint "eagle-import:0402_RES")
      (description "RES SMD 10 OHM 1% 1/16W 0402")
      (fields (field (name "MANUFACTURER") "Yageo") (field (name "MPN") "RC0402FR-0710RL"))
      (libsource (lib "eagle-import") (part "RESISTOR0402_RES"))
    )
    (comp (ref "R3")
      (value "10")
      (footprint "eagle-import:0402_RES")
      (description "RES SMD 10 OHM 1% 1/16W 0402")
      (fields (field (name "MANUFACTURER") "Yageo") (field (name "MPN") "RC0402FR-0710RL"))
      (libsource (lib "eagle-import") (part "RESISTOR0402_RES"))
    )
    (comp (ref "R6")
      (value "1.00k")
      (footprint "eagle-import:0402_RES")
      (description "RES SMD 1K OHM 0.1% 1/16W 0402")
      (fields (field (name "MANUFACTURER") "Yageo") (field (name "MPN") "RT0402BRE071KL"))
      (libsource (lib "eagle-import") (part "RESISTOR0402_RES"))
    )
    (comp (ref "R7")
      (value "1.00k")
      (footprint "eagle-import:0402_RES")
      (description "RES SMD 1K OHM 0.1% 1/16W 0402")
      (fields (field (name "MANUFACTURER") "Yageo") (field (name "MPN") "RT0402BRE071KL"))
      (libsource (lib "eagle-import") (part "RESISTOR0402_RES"))
    )
    (comp (ref "R10")
      (value "3.74k")
      (footprint "eagle-import:0402_RES")
      (description "RES SMD 3.74KOHM 0.1% 1/16W 0402")
      (fields
        (field (name "MANUFACTURER") "Panasonic Electronic Components")
        (field (name "MPN") "ERA-2AEB3741X")
      )
      (libsource (lib "eagle-import") (part "RESISTOR0402_RES"))
    )
    (comp (ref "R11")
      (value "3.74k")
      (footprint "eagle-import:0402_RES")
      (description "RES SMD 3.74KOHM 0.1% 1/16W 0402")
      (fields
        (field (name "MANUFACTURER") "Panasonic Electronic Components")
        (field (name "MPN") "ERA-2AEB3741X")
      )
      (libsource (lib "eagle-import") (part "RESISTOR0402_RES"))
    )
    (comp (ref "R31")
      (value "100k")
      (footprint "eagle-import:0402_RES")
      (description "RES SMD 100K OHM 1% 1/16W 0402")
      (fields (field (name "MANUFACTURER") "Yageo") (field (name "MPN") "RC0402FR-07100KL"))
      (libsource (lib "eagle-import") (part "RESISTOR0402_RES"))
    )
    (comp (ref "R34")
      (value "953k")
      (footprint "eagle-import:0805_RES")
      (description "RES SMD 953K OHM 0.1% 1/8W 0805")
      (fields
        (field (name "MANUFACTURER") "Panasonic Electronic Components")
        (field (name "MPN") "ERA-6AEB9533V")
      )
      (libsource (lib "eagle-import") (part "RESISTOR0805_RES"))
    )
    (comp (ref "R35")
      (value "953k")
      (footprint "eagle-import:0805_RES")
      (description "RES SMD 953K OHM 0.1% 1/8W 0805")
      (fields
        (field (name "MANUFACTURER") "Panasonic Electronic Components")
        (field (name "MPN") "ERA-6AEB9533V")
      )
      (libsource (lib "eagle-import") (part "RESISTOR0805_RES"))
    )
    (comp (ref "R36")
      (value "953k")
      (footprint "eagle-import:0805_RES")
      (description "RES SMD 953K OHM 0.1% 1/8W 0805")
      (fields
        (field (name "MANUFACTURER") "Panasonic Electronic Components")
        (field (name "MPN") "ERA-6AEB9533V")
      )
      (libsource (lib "eagle-import") (part "RESISTOR0805_RES"))
    )
    (comp (ref "R37")
      (value "953k")
      (footprint "eagle-import:0805_RES")
      (description "RES SMD 953K OHM 0.1% 1/8W 0805")
      (fields
        (field (name "MANUFACTURER") "Panasonic Electronic Components")
        (field (name "MPN") "ERA-6AEB9533V")
      )
      (libsource (lib "eagle-import") (part "RESISTOR0805_RES"))
    )
    (comp (ref "R38")
      (value "953k")
      (footprint "eagle-import:0805_RES")
      (description "RES SMD 953K OHM 0.1% 1/8W 0805")
      (fields
        (field (name "MANUFACTURER") "Panasonic Electronic Components")
        (field (name "MPN") "ERA-6AEB9533V")
      )
      (libsource (lib "eagle-import") (part "RESISTOR0805_RES"))
    )
    (comp (ref "R39")
      (value "953k")
      (footprint "eagle-import:0805_RES")
      (description "RES SMD 953K OHM 0.1% 1/8W 0805")
      (fields
        (field (name "MANUFACTURER") "Panasonic Electronic Components")
        (field (name "MPN") "ERA-6AEB9533V")
      )
      (libsource (lib "eagle-import") (part "RESISTOR0805_RES"))
    )
    (comp (ref "R40")
      (value "953k")
      (footprint "eagle-import:0805_RES")
      (description "RES SMD 953K OHM 0.1% 1/8W 0805")
      (fields
        (field (name "MANUFACTURER") "Panasonic Electronic Components")
        (field (name "MPN") "ERA-6AEB9533V")
      )
      (libsource (lib "eagle-import") (part "RESISTOR0805_RES"))
    )
    (comp (ref "R41")
      (value "953k")
      (footprint "eagle-import:0805_RES")
      (description "RES SMD 953K OHM 0.1% 1/8W 0805")
      (fields
        (field (name "MANUFACTURER") "Panasonic Electronic Components")
        (field (name "MPN") "ERA-6AEB9533V")
      )
      (libsource (lib "eagle-import") (part "RESISTOR0805_RES"))
    )
    (comp (ref "TP1")
      (value "TEST_POINT_0.040IN")
      (footprint "eagle-import:TESTPOINT_0.040IN")
      (description "7cm, 18AWG wire with 4mm stripped on each end. Attach to bottom of board. Ask for clarification.")
      (libsource (lib "eagle-import") (part "TEST_POINT_0.040IN"))
    )
    (comp (ref "TP2")
      (value "TEST_POINT_0.040IN")
      (footprint "eagle-import:TESTPOINT_0.040IN")
      (description "7cm, 18AWG wire with 4mm stripped on each end. Attach to bottom of board. Ask for clarification.")
      (libsource (lib "eagle-import") (part "TEST_POINT_0.040IN"))
    )
    (comp (ref "U2")
      (value "ADA4096-4ACPZ-R7")
      (footprint "eagle-import:CP_16_27")
      (description "IC OPAMP GP 4 CIRCUIT 16LFCSP")
      (fields
        (field (name "MANUFACTURER_PART_NUMBER") "ADA40964ACPZR7")
        (field (name "DIGIKEY") "ADA4096-4ACPZ-R7CT-ND")
        (field (name "MANUFACTURER") "Analog Devices Inc.")
        (field (name "MPN") "ADA4096-4ACPZ-R7")
      )
      (libsource (lib "eagle-import") (part "ADA4096-4ACPZ-R7"))
    )
    (comp (ref "U6")
      (value "IRM-03-5V")
      (footprint "eagle-import:IRM-03")
      (fields (field (name "MANUFACTURER") "Mean Well USA") (field (name "MPN") "IRM-03-5"))
      (libsource (lib "eagle-import") (part "IRM-03-5V"))
    )
    (comp (ref "U11")
      (value "REF2030AIDDCR")
      (footprint "eagle-import:DDC5")
      (description "IC VREF SERIES 1.5V/3V 5SOT")
      (fields
        (field (name "MANUFACTURER_PART_NUMBER") "REF2033AIDDCR")
        (field (name "DIGIKEY") "296-47351-1-ND")
        (field (name "MANUFACTURER") "Texas Instruments")
        (field (name "MANUFACTURER_PART_NUMBER_1") "REF2030AIDDCR")
        (field (name "MPN") "REF2030AIDDCR")
      )
      (libsource (lib "eagle-import") (part "REF2033AIDDCR"))
    )
    (comp (ref "U14")
      (value "SIP32510")
      (footprint "eagle-import:TSOT23-6")
      (fields (field (name "MANUFACTURER") "Vishay") (field (name "MPN") "SIP32510DT-T1-GE3"))
      (libsource (lib "eagle-import") (part "SIP32510"))
    )
    (comp (ref "V1")
      (value "S14K385")
      (footprint "eagle-import:S14K385")
      (description "VARISTOR 620V 5KA DISC 14MM")
      (fields (field (name "MANUFACTURER") "EPCOS (TDK)") (field (name "MPN") "B72214S2381K101"))
      (libsource (lib "eagle-import") (part "S14K385"))
    )
    (comp (ref "C9")
      (value "0.1uF")
      (footprint "eagle-import:0402_CAP")
      (description "CAP CER 0.1UF 10V X5R 0402")
      (fields (field (name "MANUFACTURER") "Yageo") (field (name "MPN") "CC0402KRX5R6BB104"))
      (libsource (lib "eagle-import") (part "CAPACITOR0402_CAP"))
    )
    (comp (ref "C25")
      (value "10uF")
      (footprint "eagle-import:0402_CAP")
      (description "CAP CER 10UF 6.3V X5R 0402")
      (fields
        (field (name "MANUFACTURER") "Murata Electronics North America")
        (field (name "MPN") "GRJ155R60J106ME11D")
      )
      (libsource (lib "eagle-import") (part "CAPACITOR0402_CAP"))
    )
    (comp (ref "R13")
      (value "10k")
      (footprint "eagle-import:0402_RES")
      (description "RES SMD 10K OHM 1% 1/16W 0402")
      (fields
        (field (name "MANUFACTURER") "Stackpole Electronics Inc. ")
        (field (name "MPN") "RMCF0402FT10K0 ")
      )
      (libsource (lib "eagle-import") (part "RESISTOR0402_RES"))
    )
    (comp (ref "R17")
      (value "10k")
      (footprint "eagle-import:0402_RES")
      (description "RES SMD 10K OHM 1% 1/16W 0402")
      (fields
        (field (name "MANUFACTURER") "Stackpole Electronics Inc. ")
        (field (name "MPN") "RMCF0402FT10K0 ")
      )
      (libsource (lib "eagle-import") (part "RESISTOR0402_RES"))
    )
    (comp (ref "U7")
      (value "LIS2DH12")
      (footprint "eagle-import:LGA-12")
      (fields
        (field (name "MANUFACTURER") "STMicroelectronics")
        (field (name "MPN") "LIS2DW12TR")
        (field (name "DIGIKEY") "497-14851-1-ND")
        (field (name "MOUSER") "511-LIS2DH12TR")
        (field (name "MPN_1") "LIS2DH12TR")
      )
      (libsource (lib "eagle-import") (part "LIS2DW12"))
    )
    (comp (ref "B1")
      (value "MS518SE")
      (footprint "eagle-import:MS518SE-FL35E")
      (fields (field (name "MANUFACTURER") "Seiko") (field (name "MPN") "MS518SE-FL35E"))
      (libsource (lib "eagle-import") (part "MS518SE"))
    )
    (comp (ref "C3")
      (value "47pF")
      (footprint "eagle-import:0402_CAP")
      (description "CAP CER 47PF 100V C0G/NP0 0402")
      (fields
        (field (name "MANUFACTURER") "Murata Electronics North America")
        (field (name "MPN") "GRM1555C2A470JA01D")
      )
      (libsource (lib "eagle-import") (part "CAPACITOR0402_CAP"))
    )
    (comp (ref "C17")
      (value "0.82uF")
      (footprint "eagle-import:0402_CAP")
      (description "CAP CER 0.82UF 10V X5R 0402")
      (fields (field (name "MANUFACTURER") "Yageo") (field (name "MPN") "CC0402KRX5R6BB824"))
      (libsource (lib "eagle-import") (part "CAPACITOR0402_CAP"))
    )
    (comp (ref "C18")
      (value "1uF")
      (footprint "eagle-import:0402_CAP")
      (description "CAP CER 1UF 10V X7S 0402")
      (fields
        (field (name "MANUFACTURER") "Murata Electronics North America")
        (field (name "MPN") "GCM155C71A105KE38D")
      )
      (libsource (lib "eagle-import") (part "CAPACITOR0402_CAP"))
    )
    (comp (ref "C22")
      (value "2.2uF")
      (footprint "eagle-import:0402_CAP")
      (fields
        (field (name "MANUFACTURER") "Murata Electronics North America")
        (field (name "MPN") "GRM155C70J225KE11D")
      )
      (libsource (lib "eagle-import") (part "CAPACITOR0402_CAP"))
    )
    (comp (ref "JP1")
      (value "M024UCON-15767")
      (footprint "eagle-import:JST-2-SMD-VERT")
      (description "CONN HEADER PH TOP 2POS 2MM SMD")
      (fields
        (field (name "MANUFACTURER") "JST Sales America Inc.")
        (field (name "MPN") "B2B-PH-SM4-TB(LF)(SN)")
      )
      (libsource (lib "eagle-import") (part "M024UCON-15767"))
    )
    (comp (ref "JP2")
      (value "M024UCON-15767")
      (footprint "eagle-import:JST-2-SMD-VERT")
      (description "CONN HEADER PH TOP 2POS 2MM SMD")
      (fields
        (field (name "MANUFACTURER") "JST Sales America Inc.")
        (field (name "MPN") "B2B-PH-SM4-TB(LF)(SN)")
      )
      (libsource (lib "eagle-import") (part "M024UCON-15767"))
    )
    (comp (ref "Q1")
      (value "MOSFET-NCHANNELSMD")
      (footprint "eagle-import:SOT23-3")
      (description "MOSFET N-CH 60V 115MA SOT23-3")
      (fields
        (field (name "DIGIKEY") "2N7002-FDICT-ND")
        (field (name "MANUFACTURER") "Diodes Incorporated")
        (field (name "MPN") "2N7002-7-F")
      )
      (libsource (lib "eagle-import") (part "MOSFET-NCHANNELSMD"))
    )
    (comp (ref "R18")
      (value "10k")
      (footprint "eagle-import:0402_RES")
      (description "RES SMD 10K OHM 1% 1/16W 0402")
      (fields
        (field (name "MANUFACTURER") "Stackpole Electronics Inc. ")
        (field (name "MPN") "RMCF0402FT10K0 ")
      )
      (libsource (lib "eagle-import") (part "RESISTOR0402_RES"))
    )
    (comp (ref "R19")
      (value "10k")
      (footprint "eagle-import:0402_RES")
      (description "RES SMD 10K OHM 1% 1/16W 0402")
      (fields
        (field (name "MANUFACTURER") "Stackpole Electronics Inc. ")
        (field (name "MPN") "RMCF0402FT10K0 ")
      )
      (libsource (lib "eagle-import") (part "RESISTOR0402_RES"))
    )
    (comp (ref "R20")
      (value "10k")
      (footprint "eagle-import:0402_RES")
      (description "RES SMD 10K OHM 1% 1/16W 0402")
      (fields
        (field (name "MANUFACTURER") "Stackpole Electronics Inc. ")
        (field (name "MPN") "RMCF0402FT10K0 ")
      )
      (libsource (lib "eagle-import") (part "RESISTOR0402_RES"))
    )
    (comp (ref "R21")
      (value "10k")
      (footprint "eagle-import:0402_RES")
      (description "RES SMD 10K OHM 1% 1/16W 0402")
      (fields
        (field (name "MANUFACTURER") "Stackpole Electronics Inc. ")
        (field (name "MPN") "RMCF0402FT10K0 ")
      )
      (libsource (lib "eagle-import") (part "RESISTOR0402_RES"))
    )
    (comp (ref "R22")
      (value "10k")
      (footprint "eagle-import:0402_RES")
      (description "RES SMD 10K OHM 1% 1/16W 0402")
      (fields
        (field (name "MANUFACTURER") "Stackpole Electronics Inc. ")
        (field (name "MPN") "RMCF0402FT10K0 ")
      )
      (libsource (lib "eagle-import") (part "RESISTOR0402_RES"))
    )
    (comp (ref "R29")
      (value "100k")
      (footprint "eagle-import:0402_RES")
      (description "RES SMD 100K OHM 1% 1/16W 0402")
      (fields (field (name "MANUFACTURER") "Yageo") (field (name "MPN") "RC0402FR-07100KL"))
      (libsource (lib "eagle-import") (part "RESISTOR0402_RES"))
    )
    (comp (ref "R30")
      (value "100k")
      (footprint "eagle-import:0402_RES")
      (description "RES SMD 100K OHM 1% 1/16W 0402")
      (fields (field (name "MANUFACTURER") "Yageo") (field (name "MPN") "RC0402FR-07100KL"))
      (libsource (lib "eagle-import") (part "RESISTOR0402_RES"))
    )
    (comp (ref "R33")
      (value "825k")
      (footprint "eagle-import:0402_RES")
      (description "RES SMD 825K OHM 1% 1/10W 0402")
      (fields
        (field (name "MANUFACTURER") "Panasonic Electronic Components")
        (field (name "MPN") "ERJ-2RKF8253X")
      )
      (libsource (lib "eagle-import") (part "RESISTOR0402_RES"))
    )
    (comp (ref "R42")
      (value "1M")
      (footprint "eagle-import:0402_RES")
      (description "RES 1M OHM 1% 1/16W 0402")
      (fields
        (field (name "MANUFACTURER") "Stackpole Electronics Inc ")
        (field (name "MPN") "RMCF0402FT1M00 ")
      )
      (libsource (lib "eagle-import") (part "RESISTOR0402_RES"))
    )
    (comp (ref "R43")
      (value "1M")
      (footprint "eagle-import:0402_RES")
      (description "RES 1M OHM 1% 1/16W 0402")
      (fields
        (field (name "MANUFACTURER") "Stackpole Electronics Inc ")
        (field (name "MPN") "RMCF0402FT1M00 ")
      )
      (libsource (lib "eagle-import") (part "RESISTOR0402_RES"))
    )
    (comp (ref "R44")
      (value "1M")
      (footprint "eagle-import:0402_RES")
      (description "RES 1M OHM 1% 1/16W 0402")
      (fields
        (field (name "MANUFACTURER") "Stackpole Electronics Inc ")
        (field (name "MPN") "RMCF0402FT1M00 ")
      )
      (libsource (lib "eagle-import") (part "RESISTOR0402_RES"))
    )
    (comp (ref "U1")
      (value "AB1815-T3")
      (footprint "eagle-import:QFN-16-3MM")
      (fields (field (name "MANUFACTURER") "Abracon"))
      (libsource (lib "eagle-import") (part "AB1815-T3"))
    )
    (comp (ref "U9")
      (value "MAX67XXMAX6749MAX67XX")
      (footprint "eagle-import:SOT-23-8")
      (fields (field (name "MANUFACTURER") "Maxim Integrated") (field (name "MPN") "MAX6749KA+T"))
      (libsource (lib "eagle-import") (part "MAX67XXMAX67XXMAX6749"))
    )
    (comp (ref "X2")
      (value "ABS07-32.768KHZ-7-T")
      (footprint "eagle-import:2-SMD")
      (fields (field (name "MANUFACTURER") "ABRACON") (field (name "MPN") "ABS07-32.768KHZ-7-T "))
      (libsource (lib "eagle-import") (part "ABS07-32.768KHZ-7-T"))
    )
  )
  (nets
    (net (code "1") (name "5V") (class "Default")
      (node (ref "ASSY1") (pin "VIN") (pinfunction "VIN_VIN") (pintype "power_in"))
      (node (ref "C27") (pin "1") (pinfunction "1_1") (pintype "bidirectional"))
      (node (ref "C28") (pin "1") (pinfunction "1_1") (pintype "bidirectional"))
      (node (ref "C29") (pin "+") (pinfunction "+_+") (pintype "passive"))
      (node (ref "R24") (pin "1") (pinfunction "1_1") (pintype "passive"))
      (node (ref "R29") (pin "1") (pinfunction "1_1") (pintype "passive"))
      (node (ref "R43") (pin "1") (pinfunction "1_1") (pintype "passive"))
      (node (ref "U6") (pin "V+") (pinfunction "V+_V+") (pintype "bidirectional"))
    )
    (net (code "2") (name "ACCEL_INT") (class "Default")
      (node (ref "ASSY1") (pin "C4") (pinfunction "C4_C4") (pintype "bidirectional"))
      (node (ref "U7") (pin "12") (pinfunction "INT1_12") (pintype "bidirectional"))
    )
    (net (code "3") (name "AC_COPROC_VCC") (class "Default")
      (node (ref "C15") (pin "1") (pinfunction "1_1") (pintype "bidirectional"))
      (node (ref "C16") (pin "1") (pinfunction "1_1") (pintype "bidirectional"))
      (node (ref "C20") (pin "1") (pinfunction "1_1") (pintype "bidirectional"))
      (node (ref "C21") (pin "1") (pinfunction "1_1") (pintype "bidirectional"))
      (node (ref "C24") (pin "1") (pinfunction "1_1") (pintype "bidirectional"))
      (node (ref "J2") (pin "1") (pinfunction "VCC_1") (pintype "bidirectional"))
      (node (ref "U15") (pin "1") (pinfunction "VDD_1") (pintype "bidirectional"))
      (node (ref "U15") (pin "17") (pinfunction "VDD_17") (pintype "bidirectional"))
      (node (ref "U16") (pin "3") (pinfunction "VCCA_3") (pintype "power_in"))
      (node (ref "U16") (pin "6") (pinfunction "OE_6") (pintype "input"))
      (node (ref "U17") (pin "5") (pinfunction "OUT_5") (pintype "output"))
    )
    (net (code "4") (name "AC_L_800V_DETECT") (class "Default")
      (node (ref "ASSY1") (pin "B1") (pinfunction "B1_B1") (pintype "bidirectional"))
      (node (ref "C6") (pin "1") (pinfunction "1_1") (pintype "bidirectional"))
      (node (ref "D1") (pin "C") (pinfunction "C_C") (pintype "passive"))
      (node (ref "D6") (pin "A") (pinfunction "A_A") (pintype "passive"))
      (node (ref "U15") (pin "27") (pinfunction "PB4/~{JTRST}_27") (pintype "bidirectional"))
    )
    (net (code "5") (name "AC_L_HV_OUT") (class "Default")
      (node (ref "ASSY1") (pin "A0") (pinfunction "A0_A0") (pintype "bidirectional"))
      (node (ref "R6") (pin "2") (pinfunction "2_2") (pintype "passive"))
      (node (ref "U15") (pin "6") (pinfunction "PA0/CLKIN_6") (pintype "bidirectional"))
      (node (ref "U2") (pin "14") (pinfunction "OUT_14") (pintype "bidirectional"))
    )
    (net (code "6") (name "AC_L_LV_OUT") (class "Default")
      (node (ref "ASSY1") (pin "B3") (pinfunction "B3_B3") (pintype "bidirectional"))
      (node (ref "R10") (pin "2") (pinfunction "2_2") (pintype "passive"))
      (node (ref "U15") (pin "9") (pinfunction "PA3_9") (pintype "bidirectional"))
      (node (ref "U2") (pin "7") (pinfunction "OUT_7") (pintype "bidirectional"))
    )
    (net (code "7") (name "AC_L_SENSE") (class "Default")
      (node (ref "D14") (pin "A") (pinfunction "A_A") (pintype "passive"))
      (node (ref "F1") (pin "P$2") (pinfunction "P$2_P$2") (pintype "bidirectional"))
      (node (ref "R1") (pin "1") (pinfunction "1_1") (pintype "passive"))
      (node (ref "R34") (pin "1") (pinfunction "1_1") (pintype "passive"))
      (node (ref "R39") (pin "2") (pinfunction "2_2") (pintype "passive"))
    )
    (net (code "8") (name "AC_N") (class "Default")
      (node (ref "D15") (pin "A") (pinfunction "A_A") (pintype "passive"))
      (node (ref "R36") (pin "1") (pinfunction "1_1") (pintype "passive"))
      (node (ref "R40") (pin "2") (pinfunction "2_2") (pintype "passive"))
      (node (ref "TP2") (pin "TESTPOINT") (pinfunction "TESTPOINT_TESTPOINT") (pintype "bidirectional"))
      (node (ref "U6") (pin "AC/N") (pinfunction "AC/N_AC/N") (pintype "bidirectional"))
      (node (ref "V1") (pin "2") (pinfunction "2_2") (pintype "passive"))
    )
    (net (code "9") (name "AC_N_800V_DETECT") (class "Default")
      (node (ref "ASSY1") (pin "C1") (pinfunction "C1_C1") (pintype "bidirectional"))
      (node (ref "C7") (pin "1") (pinfunction "1_1") (pintype "bidirectional"))
      (node (ref "D10") (pin "A") (pinfunction "A_A") (pintype "passive"))
      (node (ref "D2") (pin "C") (pinfunction "C_C") (pintype "passive"))
      (node (ref "U15") (pin "29") (pinfunction "PB6_29") (pintype "bidirectional"))
    )
    (net (code "10") (name "AC_N_HV_OUT") (class "Default")
      (node (ref "ASSY1") (pin "B4") (pinfunction "B4_B4") (pintype "bidirectional"))
      (node (ref "R7") (pin "2") (pinfunction "2_2") (pintype "passive"))
      (node (ref "U15") (pin "8") (pinfunction "PA2_8") (pintype "bidirectional"))
      (node (ref "U2") (pin "6") (pinfunction "OUT_6") (pintype "bidirectional"))
    )
    (net (code "11") (name "AC_N_LV_OUT") (class "Default")
      (node (ref "ASSY1") (pin "B5") (pinfunction "B5_B5") (pintype "bidirectional"))
      (node (ref "R11") (pin "1") (pinfunction "1_1") (pintype "passive"))
      (node (ref "U15") (pin "7") (pinfunction "PA1_7") (pintype "bidirectional"))
      (node (ref "U2") (pin "15") (pinfunction "OUT_15") (pintype "bidirectional"))
    )
    (net (code "12") (name "AC_SCL") (class "Default")
      (node (ref "U15") (pin "19") (pinfunction "PA9_19") (pintype "bidirectional"))
      (node (ref "U16") (pin "5") (pinfunction "SCL_A_5") (pintype "bidirectional"))
    )
    (net (code "13") (name "AC_SDA") (class "Default")
      (node (ref "U15") (pin "20") (pinfunction "PA10_20") (pintype "bidirectional"))
      (node (ref "U16") (pin "4") (pinfunction "SDA_A_4") (pintype "bidirectional"))
    )
    (net (code "14") (name "AC_SENSE_PWR_EN") (class "Default")
      (node (ref "ASSY1") (pin "C3") (pinfunction "C3_C3") (pintype "bidirectional"))
      (node (ref "R31") (pin "2") (pinfunction "2_2") (pintype "passive"))
      (node (ref "U14") (pin "3") (pinfunction "EN_3") (pintype "bidirectional"))
    )
    (net (code "15") (name "AC_SENSE_VCC") (class "Default")
      (node (ref "U11") (pin "3") (pinfunction "EN_3") (pintype "input"))
      (node (ref "U11") (pin "4") (pinfunction "VIN_4") (pintype "input"))
      (node (ref "U14") (pin "1") (pinfunction "VLOAD_1") (pintype "bidirectional"))
      (node (ref "U14") (pin "2") (pinfunction "VLOAD_2") (pintype "bidirectional"))
      (node (ref "U17") (pin "1") (pinfunction "IN_1") (pintype "input"))
      (node (ref "U17") (pin "3") (pinfunction "EN_3") (pintype "passive"))
    )
    (net (code "16") (name "ANT") (class "Default")
      (node (ref "A1") (pin "0") (pinfunction "1_0") (pintype "output"))
      (node (ref "L1") (pin "2") (pinfunction "2_2") (pintype "bidirectional"))
    )
    (net (code "17") (name "BOOT0") (class "Default")
      (node (ref "R23") (pin "2") (pinfunction "2_2") (pintype "passive"))
      (node (ref "U15") (pin "31") (pinfunction "PH3/BOOT0_31") (pintype "bidirectional"))
    )
    (net (code "18") (name "DO_NOT_CONNECT") (class "Default")
      (node (ref "ASSY1") (pin "D7") (pinfunction "D7_D7") (pintype "bidirectional"))
    )
    (net (code "19") (name "GND") (class "Default")
      (node (ref "A1") (pin "1") (pinfunction "2_1") (pintype "power_in"))
      (node (ref "A1") (pin "2") (pinfunction "2_2") (pintype "power_in"))
      (node (ref "A1") (pin "3") (pinfunction "2_3") (pintype "power_in"))
      (node (ref "A1") (pin "4") (pinfunction "2_4") (pintype "power_in"))
      (node (ref "ASSY1") (pin "GND") (pinfunction "GND_GND") (pintype "power_in"))
      (node (ref "ASSY1") (pin "GND@2") (pinfunction "GND_GND@2") (pintype "power_in"))
      (node (ref "B1") (pin "-") (pinfunction "-_-") (pintype "bidirectional"))
      (node (ref "C1") (pin "1") (pinfunction "1_1") (pintype "bidirectional"))
      (node (ref "C10") (pin "2") (pinfunction "2_2") (pintype "bidirectional"))
      (node (ref "C11") (pin "2") (pinfunction "2_2") (pintype "bidirectional"))
      (node (ref "C12") (pin "2") (pinfunction "2_2") (pintype "bidirectional"))
      (node (ref "C13") (pin "2") (pinfunction "2_2") (pintype "bidirectional"))
      (node (ref "C14") (pin "2") (pinfunction "2_2") (pintype "bidirectional"))
      (node (ref "C15") (pin "2") (pinfunction "2_2") (pintype "bidirectional"))
      (node (ref "C16") (pin "2") (pinfunction "2_2") (pintype "bidirectional"))
      (node (ref "C17") (pin "2") (pinfunction "2_2") (pintype "bidirectional"))
      (node (ref "C18") (pin "2") (pinfunction "2_2") (pintype "bidirectional"))
      (node (ref "C19") (pin "2") (pinfunction "2_2") (pintype "bidirectional"))
      (node (ref "C2") (pin "1") (pinfunction "1_1") (pintype "bidirectional"))
      (node (ref "C20") (pin "2") (pinfunction "2_2") (pintype "bidirectional"))
      (node (ref "C21") (pin "2") (pinfunction "2_2") (pintype "bidirectional"))
      (node (ref "C22") (pin "2") (pinfunction "2_2") (pintype "bidirectional"))
      (node (ref "C23") (pin "2") (pinfunction "2_2") (pintype "bidirectional"))
      (node (ref "C24") (pin "2") (pinfunction "2_2") (pintype "bidirectional"))
      (node (ref "C25") (pin "2") (pinfunction "2_2") (pintype "bidirectional"))
      (node (ref "C26") (pin "1") (pinfunction "1_1") (pintype "bidirectional"))
      (node (ref "C27") (pin "2") (pinfunction "2_2") (pintype "bidirectional"))
      (node (ref "C28") (pin "2") (pinfunction "2_2") (pintype "bidirectional"))
      (node (ref "C29") (pin "-") (pinfunction "-_-") (pintype "passive"))
      (node (ref "C3") (pin "2") (pinfunction "2_2") (pintype "bidirectional"))
      (node (ref "C4") (pin "1") (pinfunction "1_1") (pintype "bidirectional"))
      (node (ref "C5") (pin "1") (pinfunction "1_1") (pintype "bidirectional"))
      (node (ref "C6") (pin "2") (pinfunction "2_2") (pintype "bidirectional"))
      (node (ref "C7") (pin "2") (pinfunction "2_2") (pintype "bidirectional"))
      (node (ref "C8") (pin "1") (pinfunction "1_1") (pintype "bidirectional"))
      (node (ref "C9") (pin "2") (pinfunction "2_2") (pintype "bidirectional"))
      (node (ref "D1") (pin "A") (pinfunction "A_A") (pintype "passive"))
      (node (ref "D2") (pin "A") (pinfunction "A_A") (pintype "passive"))
      (node (ref "J1") (pin "6") (pinfunction "GND_6") (pintype "bidirectional"))
      (node (ref "J1") (pin "B") (pinfunction "B_B") (pintype "bidirectional"))
      (node (ref "J1") (pin "MOUNT0") (pinfunction "GND_MOUNT0") (pintype "bidirectional"))
      (node (ref "J1") (pin "MOUNT1") (pinfunction "GND_MOUNT1") (pintype "bidirectional"))
      (node (ref "J1") (pin "MOUNT2") (pinfunction "GND_MOUNT2") (pintype "bidirectional"))
      (node (ref "J1") (pin "MOUNT3") (pinfunction "GND_MOUNT3") (pintype "bidirectional"))
      (node (ref "J2") (pin "5") (pinfunction "GND_5") (pintype "bidirectional"))
      (node (ref "JP1") (pin "GND") (pinfunction "1_GND") (pintype "passive"))
      (node (ref "JP2") (pin "GND") (pinfunction "1_GND") (pintype "passive"))
      (node (ref "Q1") (pin "2") (pinfunction "S_2") (pintype "passive"))
      (node (ref "R18") (pin "2") (pinfunction "2_2") (pintype "passive"))
      (node (ref "R23") (pin "1") (pinfunction "1_1") (pintype "passive"))
      (node (ref "R25") (pin "2") (pinfunction "2_2") (pintype "passive"))
      (node (ref "R27") (pin "1") (pinfunction "1_1") (pintype "passive"))
      (node (ref "R28") (pin "1") (pinfunction "1_1") (pintype "passive"))
      (node (ref "R30") (pin "2") (pinfunction "2_2") (pintype "passive"))
      (node (ref "R31") (pin "1") (pinfunction "1_1") (pintype "passive"))
      (node (ref "R35") (pin "1") (pinfunction "1_1") (pintype "passive"))
      (node (ref "R37") (pin "1") (pinfunction "1_1") (pintype "passive"))
      (node (ref "R38") (pin "2") (pinfunction "2_2") (pintype "passive"))
      (node (ref "R41") (pin "2") (pinfunction "2_2") (pintype "passive"))
      (node (ref "R42") (pin "2") (pinfunction "2_2") (pintype "passive"))
      (node (ref "R44") (pin "2") (pinfunction "2_2") (pintype "passive"))
      (node (ref "R9") (pin "1") (pinfunction "1_1") (pintype "passive"))
      (node (ref "S1") (pin "1") (pinfunction "P$1_1") (pintype "passive"))
      (node (ref "U1") (pin "3") (pinfunction "~{EXTR}_3") (pintype "bidirectional"))
      (node (ref "U1") (pin "GND") (pinfunction "VSS_GND") (pintype "bidirectional"))
      (node (ref "U10") (pin "17") (pinfunction "EPAD_17") (pintype "power_in"))
      (node (ref "U10") (pin "6") (pinfunction "GND_6") (pintype "power_in"))
      (node (ref "U11") (pin "2") (pinfunction "GND_2") (pintype "power_in"))
      (node (ref "U12") (pin "4") (pinfunction "GND_4") (pintype "bidirectional"))
      (node (ref "U13") (pin "4") (pinfunction "GND_4") (pintype "bidirectional"))
      (node (ref "U14") (pin "4") (pinfunction "GND_4") (pintype "bidirectional"))
      (node (ref "U15") (pin "16") (pinfunction "VSS_16") (pintype "bidirectional"))
      (node (ref "U15") (pin "32") (pinfunction "VSS_32") (pintype "bidirectional"))
      (node (ref "U15") (pin "THERMAL") (pinfunction "VSS_THERMAL") (pintype "bidirectional"))
      (node (ref "U16") (pin "2") (pinfunction "GND_2") (pintype "power_in"))
      (node (ref "U17") (pin "2") (pinfunction "GND_2") (pintype "power_in"))
      (node (ref "U2") (pin "10") (pinfunction "V-_10") (pintype "bidirectional"))
      (node (ref "U2") (pin "17") (pinfunction "V-_17") (pintype "bidirectional"))
      (node (ref "U3") (pin "1") (pinfunction "GND_1") (pintype "power_in"))
      (node (ref "U3") (pin "4") (pinfunction "GND_4") (pintype "power_in"))
      (node (ref "U4") (pin "1") (pinfunction "GND_1") (pintype "power_in"))
      (node (ref "U5") (pin "2") (pinfunction "GND_2") (pintype "power_in"))
      (node (ref "U5") (pin "3") (pinfunction "GND_3") (pintype "power_in"))
      (node (ref "U5") (pin "5") (pinfunction "GND_5") (pintype "power_in"))
      (node (ref "U6") (pin "V-") (pinfunction "V-_V-") (pintype "bidirectional"))
      (node (ref "U7") (pin "3") (pinfunction "MISO/SA0_3") (pintype "bidirectional"))
      (node (ref "U7") (pin "5") (pinfunction "GND_5") (pintype "bidirectional"))
      (node (ref "U7") (pin "6") (pinfunction "GND_6") (pintype "bidirectional"))
      (node (ref "U7") (pin "7") (pinfunction "GND_7") (pintype "bidirectional"))
      (node (ref "U7") (pin "8") (pinfunction "GND_8") (pintype "bidirectional"))
      (node (ref "U8") (pin "1") (pinfunction "GND_1") (pintype "bidirectional"))
      (node (ref "U8") (pin "10") (pinfunction "GND_10") (pintype "bidirectional"))
      (node (ref "U8") (pin "12") (pinfunction "GND_12") (pintype "bidirectional"))
      (node (ref "U9") (pin "4") (pinfunction "GND_4") (pintype "bidirectional"))
    )
    (net (code "20") (name "GPS_PPS") (class "Default")
      (node (ref "ASSY1") (pin "D4") (pinfunction "D4_D4") (pintype "bidirectional"))
      (node (ref "U15") (pin "26") (pinfunction "PB3/JTDO/SWO_26") (pintype "bidirectional"))
      (node (ref "U8") (pin "4") (pinfunction "TIMEPULSE_4") (pintype "bidirectional"))
    )
    (net (code "21") (name "GPS_PWR_EN") (class "Default")
      (node (ref "ASSY1") (pin "C0") (pinfunction "C0_C0") (pintype "bidirectional"))
      (node (ref "R28") (pin "2") (pinfunction "2_2") (pintype "passive"))
      (node (ref "U12") (pin "3") (pinfunction "EN_3") (pintype "bidirectional"))
    )
    (net (code "22") (name "GPS_RXD") (class "Default")
      (node (ref "ASSY1") (pin "TX") (pinfunction "TX_TX") (pintype "bidirectional"))
      (node (ref "L3") (pin "2") (pinfunction "P$2_2") (pintype "bidirectional"))
    )
    (net (code "23") (name "GPS_TXD") (class "Default")
      (node (ref "ASSY1") (pin "RX") (pinfunction "RX_RX") (pintype "bidirectional"))
      (node (ref "L2") (pin "2") (pinfunction "P$2_2") (pintype "bidirectional"))
    )
    (net (code "24") (name "GPS_VCC") (class "Default")
      (node (ref "C26") (pin "2") (pinfunction "2_2") (pintype "bidirectional"))
      (node (ref "C5") (pin "2") (pinfunction "2_2") (pintype "bidirectional"))
      (node (ref "C8") (pin "2") (pinfunction "2_2") (pintype "bidirectional"))
      (node (ref "U12") (pin "1") (pinfunction "VLOAD_1") (pintype "bidirectional"))
      (node (ref "U12") (pin "2") (pinfunction "VLOAD_2") (pintype "bidirectional"))
      (node (ref "U8") (pin "6") (pinfunction "V_BCKP_6") (pintype "bidirectional"))
      (node (ref "U8") (pin "7") (pinfunction "VCC_IO_7") (pintype "bidirectional"))
      (node (ref "U8") (pin "8") (pinfunction "VCC_8") (pintype "bidirectional"))
    )
    (net (code "25") (name "Net-(D5-ANODE)") (class "Default")
      (node (ref "D5") (pin "A") (pinfunction "ANODE_A") (pintype "bidirectional"))
      (node (ref "U15") (pin "15") (pinfunction "PB1_15") (pintype "bidirectional"))
    )
    (net (code "26") (name "Net-(D5-CATHODE)") (class "Default")
      (node (ref "D5") (pin "C") (pinfunction "CATHODE_C") (pintype "bidirectional"))
      (node (ref "R9") (pin "2") (pinfunction "2_2") (pintype "passive"))
    )
    (net (code "27") (name "Net-(D6-PadC)") (class "Default")
      (node (ref "D6") (pin "C") (pinfunction "C_C") (pintype "passive"))
      (node (ref "D7") (pin "A") (pinfunction "A_A") (pintype "passive"))
    )
    (net (code "28") (name "Net-(D7-PadC)") (class "Default")
      (node (ref "D7") (pin "C") (pinfunction "C_C") (pintype "passive"))
      (node (ref "D8") (pin "A") (pinfunction "A_A") (pintype "passive"))
    )
    (net (code "29") (name "Net-(D8-PadC)") (class "Default")
      (node (ref "D8") (pin "C") (pinfunction "C_C") (pintype "passive"))
      (node (ref "D9") (pin "A") (pinfunction "A_A") (pintype "passive"))
    )
    (net (code "30") (name "Net-(D9-PadC)") (class "Default")
      (node (ref "D9") (pin "C") (pinfunction "C_C") (pintype "passive"))
      (node (ref "R2") (pin "1") (pinfunction "1_1") (pintype "passive"))
    )
    (net (code "31") (name "Net-(D10-PadC)") (class "Default")
      (node (ref "D10") (pin "C") (pinfunction "C_C") (pintype "passive"))
      (node (ref "D11") (pin "A") (pinfunction "A_A") (pintype "passive"))
    )
    (net (code "32") (name "Net-(D11-PadC)") (class "Default")
      (node (ref "D11") (pin "C") (pinfunction "C_C") (pintype "passive"))
      (node (ref "D12") (pin "A") (pinfunction "A_A") (pintype "passive"))
    )
    (net (code "33") (name "Net-(D12-PadC)") (class "Default")
      (node (ref "D12") (pin "C") (pinfunction "C_C") (pintype "passive"))
      (node (ref "D13") (pin "A") (pinfunction "A_A") (pintype "passive"))
    )
    (net (code "34") (name "Net-(D13-PadC)") (class "Default")
      (node (ref "D13") (pin "C") (pinfunction "C_C") (pintype "passive"))
      (node (ref "R3") (pin "1") (pinfunction "1_1") (pintype "passive"))
    )
    (net (code "35") (name "Net-(D14-PadC)") (class "Default")
      (node (ref "D14") (pin "C") (pinfunction "C_C") (pintype "passive"))
      (node (ref "R2") (pin "2") (pinfunction "2_2") (pintype "passive"))
    )
    (net (code "36") (name "Net-(D15-PadC)") (class "Default")
      (node (ref "D15") (pin "C") (pinfunction "C_C") (pintype "passive"))
      (node (ref "R3") (pin "2") (pinfunction "2_2") (pintype "passive"))
    )
    (net (code "37") (name "Net-(D29-B)") (class "Default")
      (node (ref "D29") (pin "3") (pinfunction "B_3") (pintype "output"))
      (node (ref "R4") (pin "1") (pinfunction "1_1") (pintype "passive"))
    )
    (net (code "38") (name "Net-(D29-G)") (class "Default")
      (node (ref "D29") (pin "4") (pinfunction "G_4") (pintype "output"))
      (node (ref "R5") (pin "1") (pinfunction "1_1") (pintype "passive"))
    )
    (net (code "39") (name "Net-(D29-R)") (class "Default")
      (node (ref "D29") (pin "2") (pinfunction "R_2") (pintype "output"))
      (node (ref "R8") (pin "1") (pinfunction "1_1") (pintype "passive"))
    )
    (net (code "40") (name "Net-(F1-PadP$1)") (class "Default")
      (node (ref "F1") (pin "P$1") (pinfunction "P$1_P$1") (pintype "bidirectional"))
      (node (ref "TP1") (pin "TESTPOINT") (pinfunction "TESTPOINT_TESTPOINT") (pintype "bidirectional"))
    )
    (net (code "41") (name "Net-(J1-VCC)") (class "Default")
      (node (ref "C23") (pin "1") (pinfunction "1_1") (pintype "bidirectional"))
      (node (ref "J1") (pin "4") (pinfunction "VCC_4") (pintype "bidirectional"))
      (node (ref "R14") (pin "2") (pinfunction "2_2") (pintype "passive"))
      (node (ref "R15") (pin "2") (pinfunction "2_2") (pintype "passive"))
      (node (ref "R16") (pin "2") (pinfunction "2_2") (pintype "passive"))
      (node (ref "R26") (pin "2") (pinfunction "2_2") (pintype "passive"))
      (node (ref "U13") (pin "1") (pinfunction "VLOAD_1") (pintype "bidirectional"))
      (node (ref "U13") (pin "2") (pinfunction "VLOAD_2") (pintype "bidirectional"))
    )
    (net (code "42") (name "Net-(JP1-2)") (class "Default")
      (node (ref "JP1") (pin "VCC") (pinfunction "2_VCC") (pintype "passive"))
      (node (ref "JP2") (pin "VCC") (pinfunction "2_VCC") (pintype "passive"))
      (node (ref "R21") (pin "1") (pinfunction "1_1") (pintype "passive"))
      (node (ref "R33") (pin "1") (pinfunction "1_1") (pintype "passive"))
      (node (ref "U9") (pin "5") (pinfunction "WDS_5") (pintype "bidirectional"))
      (node (ref "U9") (pin "8") (pinfunction "VCC_8") (pintype "bidirectional"))
    )
    (net (code "43") (name "Net-(L2-P$1)") (class "Default")
      (node (ref "L2") (pin "1") (pinfunction "P$1_1") (pintype "bidirectional"))
      (node (ref "U8") (pin "2") (pinfunction "TXD_2") (pintype "bidirectional"))
    )
    (net (code "44") (name "Net-(L3-P$1)") (class "Default")
      (node (ref "L3") (pin "1") (pinfunction "P$1_1") (pintype "bidirectional"))
      (node (ref "U8") (pin "3") (pinfunction "RXD_3") (pintype "bidirectional"))
    )
    (net (code "45") (name "Net-(Q1-D)") (class "Default")
      (node (ref "Q1") (pin "3") (pinfunction "D_3") (pintype "passive"))
      (node (ref "R33") (pin "2") (pinfunction "2_2") (pintype "passive"))
      (node (ref "R42") (pin "1") (pinfunction "1_1") (pintype "passive"))
      (node (ref "R43") (pin "2") (pinfunction "2_2") (pintype "passive"))
      (node (ref "U9") (pin "1") (pinfunction "~{MR}_1") (pintype "bidirectional"))
    )
    (net (code "46") (name "Net-(Q2-D)") (class "Default")
      (node (ref "ASSY1") (pin "WKP") (pinfunction "WKP_WKP") (pintype "bidirectional"))
      (node (ref "Q2") (pin "3") (pinfunction "D_3") (pintype "passive"))
      (node (ref "R24") (pin "2") (pinfunction "2_2") (pintype "passive"))
      (node (ref "R25") (pin "1") (pinfunction "1_1") (pintype "passive"))
    )
    (net (code "47") (name "Net-(R1-Pad2)") (class "Default")
      (node (ref "R1") (pin "2") (pinfunction "2_2") (pintype "passive"))
      (node (ref "U6") (pin "AC/L") (pinfunction "AC/L_AC/L") (pintype "bidirectional"))
      (node (ref "V1") (pin "1") (pinfunction "1_1") (pintype "passive"))
    )
    (net (code "48") (name "Net-(U1-AF)") (class "Default")
      (node (ref "C3") (pin "1") (pinfunction "1_1") (pintype "bidirectional"))
      (node (ref "U1") (pin "14") (pinfunction "AF_14") (pintype "bidirectional"))
    )
    (net (code "49") (name "Net-(U1-EXTI)") (class "Default")
      (node (ref "R29") (pin "2") (pinfunction "2_2") (pintype "passive"))
      (node (ref "R30") (pin "1") (pinfunction "1_1") (pintype "passive"))
      (node (ref "U1") (pin "10") (pinfunction "EXTI_10") (pintype "bidirectional"))
    )
    (net (code "50") (name "Net-(U1-VBAT)") (class "Default")
      (node (ref "B1") (pin "+") (pinfunction "+_+") (pintype "bidirectional"))
      (node (ref "R22") (pin "1") (pinfunction "1_1") (pintype "passive"))
      (node (ref "U1") (pin "5") (pinfunction "VBAT_5") (pintype "bidirectional"))
    )
    (net (code "51") (name "Net-(U1-XI)") (class "Default")
      (node (ref "U1") (pin "16") (pinfunction "XI_16") (pintype "bidirectional"))
      (node (ref "X2") (pin "1") (pinfunction "1_1") (pintype "bidirectional"))
    )
    (net (code "52") (name "Net-(U1-XO)") (class "Default")
      (node (ref "U1") (pin "15") (pinfunction "XO_15") (pintype "bidirectional"))
      (node (ref "X2") (pin "2") (pinfunction "2_2") (pintype "bidirectional"))
    )
    (net (code "53") (name "Net-(U2A--)") (class "Default")
      (node (ref "R11") (pin "2") (pinfunction "2_2") (pintype "passive"))
      (node (ref "R36") (pin "2") (pinfunction "2_2") (pintype "passive"))
      (node (ref "R37") (pin "2") (pinfunction "2_2") (pintype "passive"))
      (node (ref "U2") (pin "1") (pinfunction "-_1") (pintype "bidirectional"))
    )
    (net (code "54") (name "Net-(U2B--)") (class "Default")
      (node (ref "R40") (pin "1") (pinfunction "1_1") (pintype "passive"))
      (node (ref "R41") (pin "1") (pinfunction "1_1") (pintype "passive"))
      (node (ref "R7") (pin "1") (pinfunction "1_1") (pintype "passive"))
      (node (ref "U2") (pin "5") (pinfunction "-_5") (pintype "bidirectional"))
    )
    (net (code "55") (name "Net-(U2C--)") (class "Default")
      (node (ref "R10") (pin "1") (pinfunction "1_1") (pintype "passive"))
      (node (ref "R34") (pin "2") (pinfunction "2_2") (pintype "passive"))
      (node (ref "R35") (pin "2") (pinfunction "2_2") (pintype "passive"))
      (node (ref "U2") (pin "8") (pinfunction "-_8") (pintype "bidirectional"))
    )
    (net (code "56") (name "Net-(U2D--)") (class "Default")
      (node (ref "R38") (pin "1") (pinfunction "1_1") (pintype "passive"))
      (node (ref "R39") (pin "1") (pinfunction "1_1") (pintype "passive"))
      (node (ref "R6") (pin "1") (pinfunction "1_1") (pintype "passive"))
      (node (ref "U2") (pin "12") (pinfunction "-_12") (pintype "bidirectional"))
    )
    (net (code "57") (name "Net-(U3-AI)") (class "Default")
      (node (ref "L1") (pin "1") (pinfunction "1_1") (pintype "bidirectional"))
      (node (ref "U3") (pin "5") (pinfunction "AI_5") (pintype "input"))
    )
    (net (code "58") (name "Net-(U3-AO)") (class "Default")
      (node (ref "U3") (pin "3") (pinfunction "AO_3") (pintype "output"))
      (node (ref "U5") (pin "1") (pinfunction "INPUT_1") (pintype "input"))
    )
    (net (code "59") (name "Net-(U5-OUTPUT)") (class "Default")
      (node (ref "U5") (pin "4") (pinfunction "OUTPUT_4") (pintype "bidirectional"))
      (node (ref "U8") (pin "11") (pinfunction "RF_IN_11") (pintype "bidirectional"))
    )
    (net (code "60") (name "Net-(U9-SRT)") (class "Default")
      (node (ref "C17") (pin "1") (pinfunction "1_1") (pintype "bidirectional"))
      (node (ref "U9") (pin "3") (pinfunction "SRT_3") (pintype "bidirectional"))
    )
    (net (code "61") (name "Net-(U9-SWT)") (class "Default")
      (node (ref "C22") (pin "1") (pinfunction "1_1") (pintype "bidirectional"))
      (node (ref "U9") (pin "2") (pinfunction "SWT_2") (pintype "bidirectional"))
    )
    (net (code "62") (name "Net-(U10-P0)") (class "Default")
      (node (ref "R8") (pin "2") (pinfunction "2_2") (pintype "passive"))
      (node (ref "U10") (pin "2") (pinfunction "P0_2") (pintype "bidirectional"))
    )
    (net (code "63") (name "Net-(U10-P1)") (class "Default")
      (node (ref "R4") (pin "2") (pinfunction "2_2") (pintype "passive"))
      (node (ref "U10") (pin "3") (pinfunction "P1_3") (pintype "bidirectional"))
    )
    (net (code "64") (name "Net-(U10-P2)") (class "Default")
      (node (ref "R5") (pin "2") (pinfunction "2_2") (pintype "passive"))
      (node (ref "U10") (pin "4") (pinfunction "P2_4") (pintype "bidirectional"))
    )
    (net (code "65") (name "Net-(U15-PC14{slash}OSC32IN)") (class "Default")
      (node (ref "C1") (pin "2") (pinfunction "2_2") (pintype "bidirectional"))
      (node (ref "U15") (pin "2") (pinfunction "PC14/OSC32IN_2") (pintype "bidirectional"))
      (node (ref "X1") (pin "B") (pinfunction "2_B") (pintype "bidirectional"))
    )
    (net (code "66") (name "Net-(U15-PC15{slash}OSC32OUT)") (class "Default")
      (node (ref "C2") (pin "2") (pinfunction "2_2") (pintype "bidirectional"))
      (node (ref "U15") (pin "3") (pinfunction "PC15/OSC32OUT_3") (pintype "bidirectional"))
      (node (ref "X1") (pin "A") (pinfunction "1_A") (pintype "bidirectional"))
    )
    (net (code "67") (name "PARTICLE_RST") (class "Default")
      (node (ref "ASSY1") (pin "D3") (pinfunction "D3_D3") (pintype "bidirectional"))
      (node (ref "Q1") (pin "1") (pinfunction "G_1") (pintype "passive"))
      (node (ref "R44") (pin "1") (pinfunction "1_1") (pintype "passive"))
    )
    (net (code "68") (name "REF_1V5") (class "Default")
      (node (ref "C10") (pin "1") (pinfunction "1_1") (pintype "bidirectional"))
      (node (ref "C11") (pin "1") (pinfunction "1_1") (pintype "bidirectional"))
      (node (ref "C12") (pin "1") (pinfunction "1_1") (pintype "bidirectional"))
      (node (ref "C13") (pin "1") (pinfunction "1_1") (pintype "bidirectional"))
      (node (ref "U11") (pin "1") (pinfunction "VBIAS_1") (pintype "input"))
      (node (ref "U2") (pin "11") (pinfunction "+_11") (pintype "bidirectional"))
      (node (ref "U2") (pin "2") (pinfunction "+_2") (pintype "bidirectional"))
      (node (ref "U2") (pin "4") (pinfunction "+_4") (pintype "bidirectional"))
      (node (ref "U2") (pin "9") (pinfunction "+_9") (pintype "bidirectional"))
    )
    (net (code "69") (name "REF_3V") (class "Default")
      (node (ref "C14") (pin "1") (pinfunction "1_1") (pintype "bidirectional"))
      (node (ref "C19") (pin "1") (pinfunction "1_1") (pintype "bidirectional"))
      (node (ref "U11") (pin "5") (pinfunction "VREF_5") (pintype "output"))
      (node (ref "U15") (pin "5") (pinfunction "VDDA/VREF_5") (pintype "bidirectional"))
      (node (ref "U2") (pin "3") (pinfunction "V+_3") (pintype "bidirectional"))
    )
    (net (code "70") (name "SD_ENABLE") (class "Default")
      (node (ref "ASSY1") (pin "C2") (pinfunction "C2_C2") (pintype "bidirectional"))
      (node (ref "R27") (pin "2") (pinfunction "2_2") (pintype "passive"))
      (node (ref "U13") (pin "3") (pinfunction "EN_3") (pintype "bidirectional"))
    )
    (net (code "71") (name "SD_MISO") (class "Default")
      (node (ref "ASSY1") (pin "A4") (pinfunction "A4_A4") (pintype "bidirectional"))
      (node (ref "J1") (pin "7") (pinfunction "DATA0/MISO_7") (pintype "bidirectional"))
      (node (ref "R16") (pin "1") (pinfunction "1_1") (pintype "passive"))
      (node (ref "U1") (pin "6") (pinfunction "SDO_6") (pintype "bidirectional"))
    )
    (net (code "72") (name "SD_MOSI") (class "Default")
      (node (ref "ASSY1") (pin "A5") (pinfunction "A5_A5") (pintype "bidirectional"))
      (node (ref "J1") (pin "3") (pinfunction "CMD/MOSI_3") (pintype "bidirectional"))
      (node (ref "R14") (pin "1") (pinfunction "1_1") (pintype "passive"))
      (node (ref "U1") (pin "9") (pinfunction "SDI_9") (pintype "bidirectional"))
    )
    (net (code "73") (name "SD_SCLK") (class "Default")
      (node (ref "ASSY1") (pin "A3") (pinfunction "A3_A3") (pintype "bidirectional"))
      (node (ref "J1") (pin "5") (pinfunction "CLK_5") (pintype "bidirectional"))
      (node (ref "U1") (pin "7") (pinfunction "SCL_7") (pintype "bidirectional"))
    )
    (net (code "74") (name "SENSORS_SCL") (class "Default")
      (node (ref "ASSY1") (pin "D1") (pinfunction "D1_D1") (pintype "bidirectional"))
      (node (ref "R17") (pin "1") (pinfunction "1_1") (pintype "passive"))
      (node (ref "U10") (pin "12") (pinfunction "SCL_12") (pintype "input"))
      (node (ref "U16") (pin "8") (pinfunction "SCL_B_8") (pintype "bidirectional"))
      (node (ref "U7") (pin "1") (pinfunction "SCL/SPC_1") (pintype "bidirectional"))
    )
    (net (code "75") (name "SENSORS_SDA") (class "Default")
      (node (ref "ASSY1") (pin "D0") (pinfunction "D0_D0") (pintype "bidirectional"))
      (node (ref "R13") (pin "1") (pinfunction "1_1") (pintype "passive"))
      (node (ref "U10") (pin "13") (pinfunction "SDA_13") (pintype "bidirectional"))
      (node (ref "U16") (pin "1") (pinfunction "SDA_B_1") (pintype "bidirectional"))
      (node (ref "U7") (pin "4") (pinfunction "MOSI/SDA_4") (pintype "bidirectional"))
    )
    (net (code "76") (name "SERIAL_NUM") (class "Default")
      (node (ref "ASSY1") (pin "B0") (pinfunction "B0_B0") (pintype "bidirectional"))
      (node (ref "R12") (pin "2") (pinfunction "2_2") (pintype "passive"))
      (node (ref "U4") (pin "2") (pinfunction "DATA_2") (pintype "input"))
    )
    (net (code "77") (name "SWDCLK") (class "Default")
      (node (ref "J2") (pin "4") (pinfunction "SWDCLK_4") (pintype "bidirectional"))
      (node (ref "U15") (pin "24") (pinfunction "PA14/SWDCLK_24") (pintype "bidirectional"))
    )
    (net (code "78") (name "SWDIO") (class "Default")
      (node (ref "J2") (pin "2") (pinfunction "SWDIO_2") (pintype "bidirectional"))
      (node (ref "U15") (pin "23") (pinfunction "PA13/SWDIO_23") (pintype "bidirectional"))
    )
    (net (code "79") (name "VCC") (class "Default")
      (node (ref "ASSY1") (pin "3V3") (pinfunction "3V3_3V3") (pintype "power_in"))
      (node (ref "C18") (pin "1") (pinfunction "1_1") (pintype "bidirectional"))
      (node (ref "C25") (pin "1") (pinfunction "1_1") (pintype "bidirectional"))
      (node (ref "C9") (pin "1") (pinfunction "1_1") (pintype "bidirectional"))
      (node (ref "D29") (pin "1") (pinfunction "VDD_1") (pintype "bidirectional"))
      (node (ref "Q2") (pin "2") (pinfunction "S_2") (pintype "passive"))
      (node (ref "R12") (pin "1") (pinfunction "1_1") (pintype "passive"))
      (node (ref "R13") (pin "2") (pinfunction "2_2") (pintype "passive"))
      (node (ref "R17") (pin "2") (pinfunction "2_2") (pintype "passive"))
      (node (ref "R19") (pin "1") (pinfunction "1_1") (pintype "passive"))
      (node (ref "R20") (pin "1") (pinfunction "1_1") (pintype "passive"))
      (node (ref "R32") (pin "1") (pinfunction "1_1") (pintype "passive"))
      (node (ref "U1") (pin "13") (pinfunction "VCC_13") (pintype "bidirectional"))
      (node (ref "U10") (pin "1") (pinfunction "AD2_1") (pintype "input"))
      (node (ref "U10") (pin "14") (pinfunction "V+_14") (pintype "power_in"))
      (node (ref "U10") (pin "15") (pinfunction "AD0_15") (pintype "input"))
      (node (ref "U10") (pin "16") (pinfunction "AD1_16") (pintype "input"))
      (node (ref "U12") (pin "5") (pinfunction "VSUPP_5") (pintype "bidirectional"))
      (node (ref "U12") (pin "6") (pinfunction "VSUPP_6") (pintype "bidirectional"))
      (node (ref "U13") (pin "5") (pinfunction "VSUPP_5") (pintype "bidirectional"))
      (node (ref "U13") (pin "6") (pinfunction "VSUPP_6") (pintype "bidirectional"))
      (node (ref "U14") (pin "5") (pinfunction "VSUPP_5") (pintype "bidirectional"))
      (node (ref "U14") (pin "6") (pinfunction "VSUPP_6") (pintype "bidirectional"))
      (node (ref "U16") (pin "7") (pinfunction "VCCB_7") (pintype "power_in"))
      (node (ref "U7") (pin "10") (pinfunction "VDD_IO_10") (pintype "bidirectional"))
      (node (ref "U7") (pin "2") (pinfunction "CS_2") (pintype "bidirectional"))
      (node (ref "U7") (pin "9") (pinfunction "VCC_9") (pintype "bidirectional"))
    )
    (net (code "80") (name "VCC_RF") (class "Default")
      (node (ref "C4") (pin "2") (pinfunction "2_2") (pintype "bidirectional"))
      (node (ref "U3") (pin "2") (pinfunction "VCC_2") (pintype "power_in"))
      (node (ref "U3") (pin "6") (pinfunction "PON_6") (pintype "input"))
      (node (ref "U8") (pin "14") (pinfunction "VCC_RF_14") (pintype "bidirectional"))
    )
    (net (code "81") (name "WDI") (class "Default")
      (node (ref "ASSY1") (pin "DAC") (pinfunction "DAC_DAC") (pintype "bidirectional"))
      (node (ref "R18") (pin "1") (pinfunction "1_1") (pintype "passive"))
      (node (ref "U1") (pin "2") (pinfunction "WDI_2") (pintype "bidirectional"))
      (node (ref "U9") (pin "6") (pinfunction "WDI_6") (pintype "bidirectional"))
    )
    (net (code "82") (name "unconnected-(ASSY1-PadA1)") (class "Default")
      (node (ref "ASSY1") (pin "A1") (pinfunction "A1_A1") (pintype "bidirectional"))
    )
    (net (code "83") (name "unconnected-(ASSY1-PadB2)") (class "Default")
      (node (ref "ASSY1") (pin "B2") (pinfunction "B2_B2") (pintype "bidirectional"))
    )
    (net (code "84") (name "unconnected-(ASSY1-PadVBAT)") (class "Default")
      (node (ref "ASSY1") (pin "VBAT") (pinfunction "VBAT_VBAT") (pintype "passive"))
    )
    (net (code "85") (name "unconnected-(J1-DATA1{slash}RSV-Pad8)") (class "Default")
      (node (ref "J1") (pin "8") (pinfunction "DATA1/RSV_8") (pintype "bidirectional"))
    )
    (net (code "86") (name "unconnected-(J1-DATA2{slash}NC-Pad1)") (class "Default")
      (node (ref "J1") (pin "1") (pinfunction "DATA2/NC_1") (pintype "bidirectional"))
    )
    (net (code "87") (name "unconnected-(J2-SWO-Pad6)") (class "Default")
      (node (ref "J2") (pin "6") (pinfunction "SWO_6") (pintype "bidirectional"))
    )
    (net (code "88") (name "unconnected-(U1-CLKOUT{slash}~{IRQ3}-Pad8)") (class "Default")
      (node (ref "U1") (pin "8") (pinfunction "CLKOUT/~{IRQ3}_8") (pintype "bidirectional"))
    )
    (net (code "89") (name "unconnected-(U1-~{RST}-Pad1)") (class "Default")
      (node (ref "U1") (pin "1") (pinfunction "~{RST}_1") (pintype "bidirectional"))
    )
    (net (code "90") (name "unconnected-(U4-NC-Pad6)") (class "Default")
      (node (ref "U4") (pin "6") (pinfunction "NC_6") (pintype "no_connect"))
    )
    (net (code "91") (name "unconnected-(U4-NC_2-Pad3)") (class "Default")
      (node (ref "U4") (pin "3") (pinfunction "NC_2_3") (pintype "no_connect"))
    )
    (net (code "92") (name "unconnected-(U4-NC_3-Pad4)") (class "Default")
      (node (ref "U4") (pin "4") (pinfunction "NC_3_4") (pintype "no_connect"))
    )
    (net (code "93") (name "unconnected-(U4-NC_4-Pad5)") (class "Default")
      (node (ref "U4") (pin "5") (pinfunction "NC_4_5") (pintype "no_connect"))
    )
    (net (code "94") (name "unconnected-(U7-INT2-Pad11)") (class "Default")
      (node (ref "U7") (pin "11") (pinfunction "INT2_11") (pintype "bidirectional"))
    )
    (net (code "95") (name "unconnected-(U8-EXTINT-Pad5)") (class "Default")
      (node (ref "U8") (pin "5") (pinfunction "EXTINT_5") (pintype "bidirectional"))
    )
    (net (code "96") (name "unconnected-(U8-LNA_EN-Pad13)") (class "Default")
      (node (ref "U8") (pin "13") (pinfunction "LNA_EN_13") (pintype "bidirectional"))
    )
    (net (code "97") (name "unconnected-(U8-SCL-Pad17)") (class "Default")
      (node (ref "U8") (pin "17") (pinfunction "SCL_17") (pintype "bidirectional"))
    )
    (net (code "98") (name "unconnected-(U8-SDA-Pad16)") (class "Default")
      (node (ref "U8") (pin "16") (pinfunction "SDA_16") (pintype "bidirectional"))
    )
    (net (code "99") (name "unconnected-(U8-V_ANT-Pad15)") (class "Default")
      (node (ref "U8") (pin "15") (pinfunction "V_ANT_15") (pintype "bidirectional"))
    )
    (net (code "100") (name "unconnected-(U8-~{RESET}-Pad9)") (class "Default")
      (node (ref "U8") (pin "9") (pinfunction "~{RESET}_9") (pintype "bidirectional"))
    )
    (net (code "101") (name "unconnected-(U8-~{SAFEBOOT}-Pad18)") (class "Default")
      (node (ref "U8") (pin "18") (pinfunction "~{SAFEBOOT}_18") (pintype "bidirectional"))
    )
    (net (code "102") (name "unconnected-(U10-P3-Pad5)") (class "Default")
      (node (ref "U10") (pin "5") (pinfunction "P3_5") (pintype "bidirectional"))
    )
    (net (code "103") (name "unconnected-(U10-P4-Pad7)") (class "Default")
      (node (ref "U10") (pin "7") (pinfunction "P4_7") (pintype "bidirectional"))
    )
    (net (code "104") (name "unconnected-(U10-P5-Pad8)") (class "Default")
      (node (ref "U10") (pin "8") (pinfunction "P5_8") (pintype "bidirectional"))
    )
    (net (code "105") (name "unconnected-(U10-P6-Pad9)") (class "Default")
      (node (ref "U10") (pin "9") (pinfunction "P6_9") (pintype "bidirectional"))
    )
    (net (code "106") (name "unconnected-(U10-P7-Pad10)") (class "Default")
      (node (ref "U10") (pin "10") (pinfunction "P7_10") (pintype "bidirectional"))
    )
    (net (code "107") (name "unconnected-(U10-~{INT{slash}08}-Pad11)") (class "Default")
      (node (ref "U10") (pin "11") (pinfunction "~{INT/08}_11") (pintype "output"))
    )
    (net (code "108") (name "unconnected-(U15-PA4-Pad10)") (class "Default")
      (node (ref "U15") (pin "10") (pinfunction "PA4_10") (pintype "bidirectional"))
    )
    (net (code "109") (name "unconnected-(U15-PA5-Pad11)") (class "Default")
      (node (ref "U15") (pin "11") (pinfunction "PA5_11") (pintype "bidirectional"))
    )
    (net (code "110") (name "unconnected-(U15-PA6-Pad12)") (class "Default")
      (node (ref "U15") (pin "12") (pinfunction "PA6_12") (pintype "bidirectional"))
    )
    (net (code "111") (name "unconnected-(U15-PA7-Pad13)") (class "Default")
      (node (ref "U15") (pin "13") (pinfunction "PA7_13") (pintype "bidirectional"))
    )
    (net (code "112") (name "unconnected-(U15-PA8-Pad18)") (class "Default")
      (node (ref "U15") (pin "18") (pinfunction "PA8_18") (pintype "bidirectional"))
    )
    (net (code "113") (name "unconnected-(U15-PA11-Pad21)") (class "Default")
      (node (ref "U15") (pin "21") (pinfunction "PA11_21") (pintype "bidirectional"))
    )
    (net (code "114") (name "unconnected-(U15-PA12-Pad22)") (class "Default")
      (node (ref "U15") (pin "22") (pinfunction "PA12_22") (pintype "bidirectional"))
    )
    (net (code "115") (name "unconnected-(U15-PA15{slash}JTDI-Pad25)") (class "Default")
      (node (ref "U15") (pin "25") (pinfunction "PA15/JTDI_25") (pintype "bidirectional"))
    )
    (net (code "116") (name "unconnected-(U15-PB0-Pad14)") (class "Default")
      (node (ref "U15") (pin "14") (pinfunction "PB0_14") (pintype "bidirectional"))
    )
    (net (code "117") (name "unconnected-(U15-PB5-Pad28)") (class "Default")
      (node (ref "U15") (pin "28") (pinfunction "PB5_28") (pintype "bidirectional"))
    )
    (net (code "118") (name "unconnected-(U15-PB7-Pad30)") (class "Default")
      (node (ref "U15") (pin "30") (pinfunction "PB7_30") (pintype "bidirectional"))
    )
    (net (code "119") (name "unconnected-(U17-NR-Pad4)") (class "Default")
      (node (ref "U17") (pin "4") (pinfunction "NR_4") (pintype "passive"))
    )
    (net (code "120") (name "~{EXTERNAL_RST}") (class "Default")
      (node (ref "ASSY1") (pin "RST") (pinfunction "RST_RST") (pintype "bidirectional"))
      (node (ref "R21") (pin "2") (pinfunction "2_2") (pintype "passive"))
      (node (ref "U9") (pin "7") (pinfunction "~{RESET}_7") (pintype "bidirectional"))
    )
    (net (code "121") (name "~{RST}") (class "Default")
      (node (ref "J2") (pin "3") (pinfunction "~{RESET}_3") (pintype "bidirectional"))
      (node (ref "S1") (pin "2") (pinfunction "P$2_2") (pintype "passive"))
      (node (ref "U15") (pin "4") (pinfunction "~{RST}_4") (pintype "bidirectional"))
    )
    (net (code "122") (name "~{RTC_CS}") (class "Default")
      (node (ref "ASSY1") (pin "C5") (pinfunction "C5_C5") (pintype "bidirectional"))
      (node (ref "R20") (pin "2") (pinfunction "2_2") (pintype "passive"))
      (node (ref "R22") (pin "2") (pinfunction "2_2") (pintype "passive"))
      (node (ref "U1") (pin "12") (pinfunction "~{CS}_12") (pintype "bidirectional"))
    )
    (net (code "123") (name "~{RTC_INT1}") (class "Default")
      (node (ref "ASSY1") (pin "D5") (pinfunction "D5_D5") (pintype "bidirectional"))
      (node (ref "R19") (pin "2") (pinfunction "2_2") (pintype "passive"))
      (node (ref "U1") (pin "11") (pinfunction "FOUT/~{IRQ1}_11") (pintype "bidirectional"))
    )
    (net (code "124") (name "~{RTC_INT2}") (class "Default")
      (node (ref "ASSY1") (pin "D2") (pinfunction "D2_D2") (pintype "bidirectional"))
      (node (ref "Q2") (pin "1") (pinfunction "G_1") (pintype "passive"))
      (node (ref "R32") (pin "2") (pinfunction "2_2") (pintype "passive"))
      (node (ref "U1") (pin "4") (pinfunction "~{IRQ2}_4") (pintype "bidirectional"))
    )
    (net (code "125") (name "~{SD_CS}") (class "Default")
      (node (ref "ASSY1") (pin "A2") (pinfunction "A2_A2") (pintype "bidirectional"))
      (node (ref "J1") (pin "2") (pinfunction "DATA3-CD/CS_N_2") (pintype "bidirectional"))
      (node (ref "R15") (pin "1") (pinfunction "1_1") (pintype "passive"))
    )
    (net (code "126") (name "~{SD_DETECT}") (class "Default")
      (node (ref "ASSY1") (pin "D6") (pinfunction "D6_D6") (pintype "bidirectional"))
      (node (ref "J1") (pin "A") (pinfunction "A_A") (pintype "bidirectional"))
      (node (ref "R26") (pin "1") (pinfunction "1_1") (pintype "passive"))
    )
  )
)
